# io-board-e-6.net
KiCad netlist of a schematic drawn in EAGLE
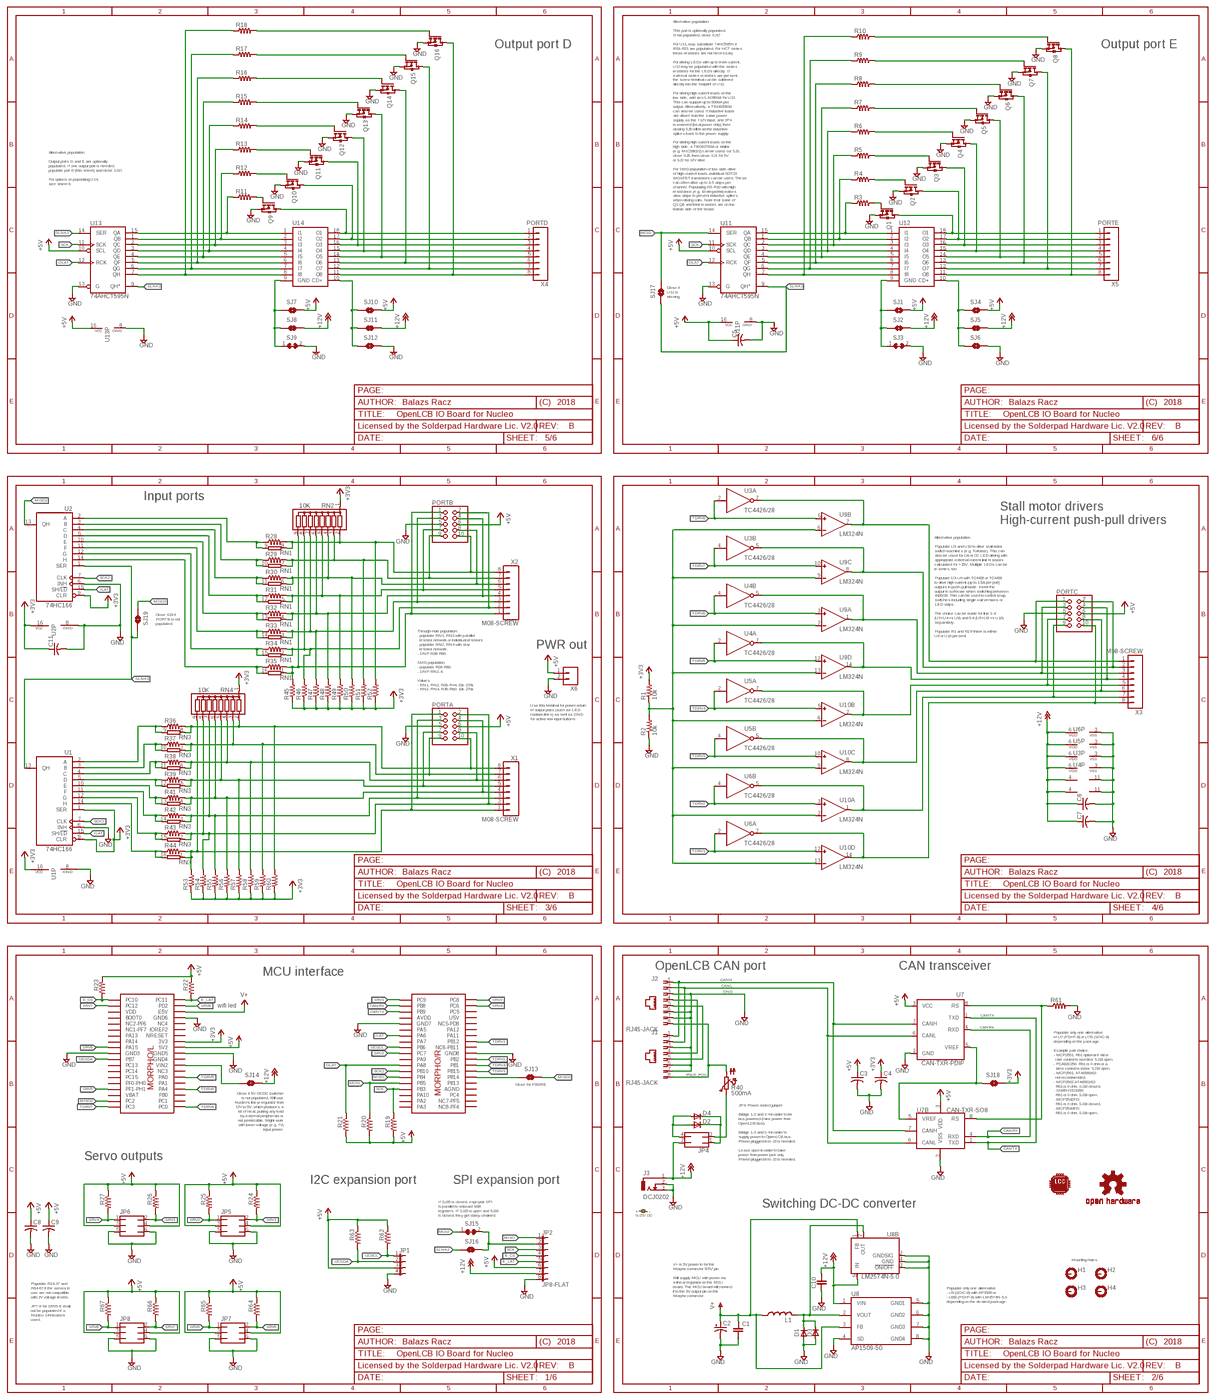
[diagram p0: schematic, sheet 1, overview]
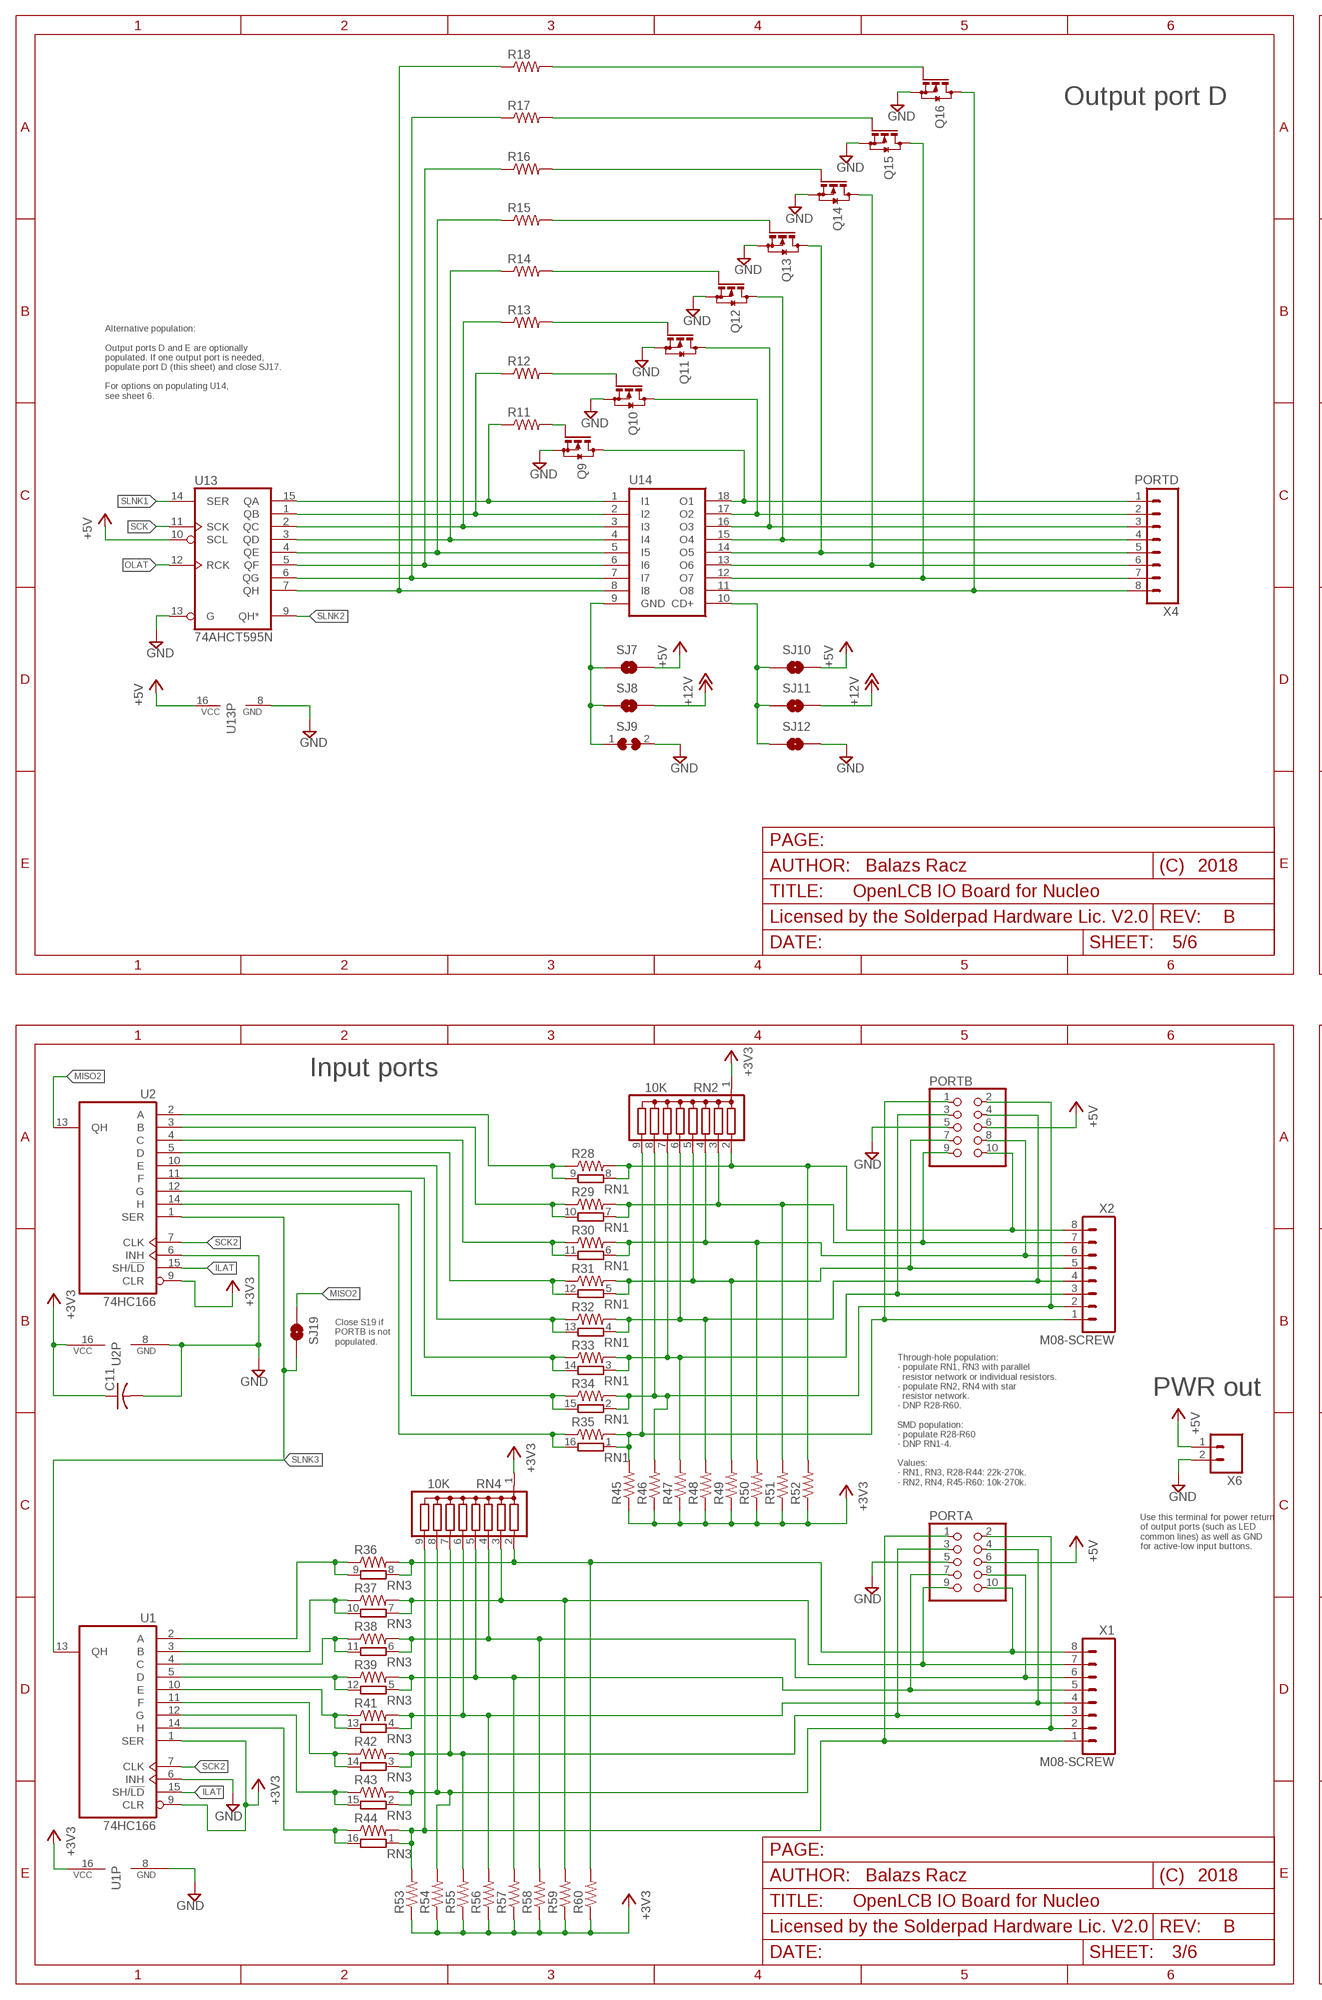
[diagram p1: schematic, sheet 1, part 1 of 4]
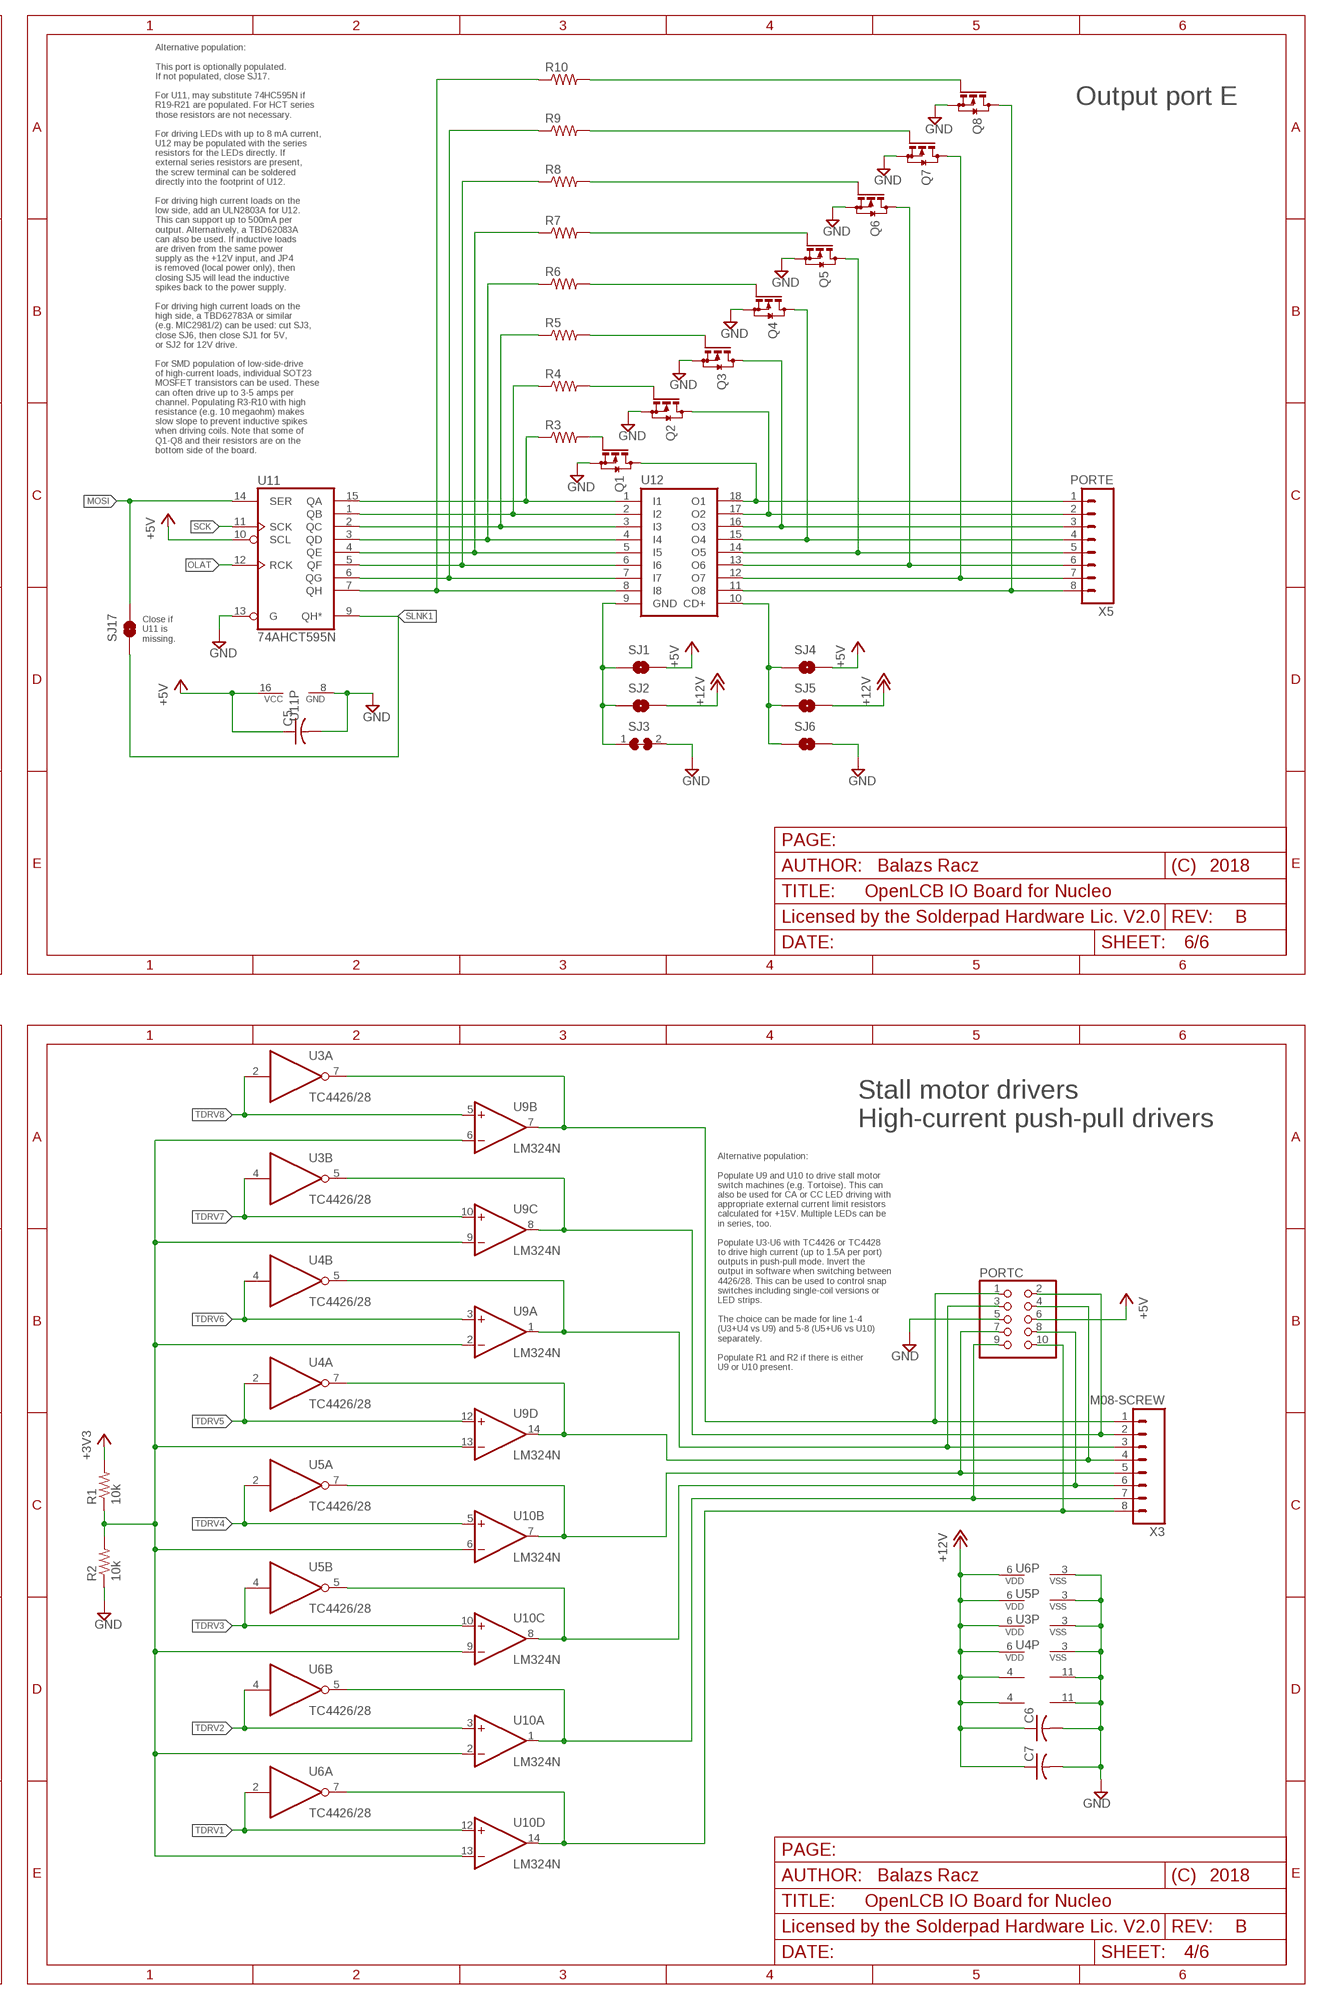
[diagram p2: schematic, sheet 1, part 2 of 4]
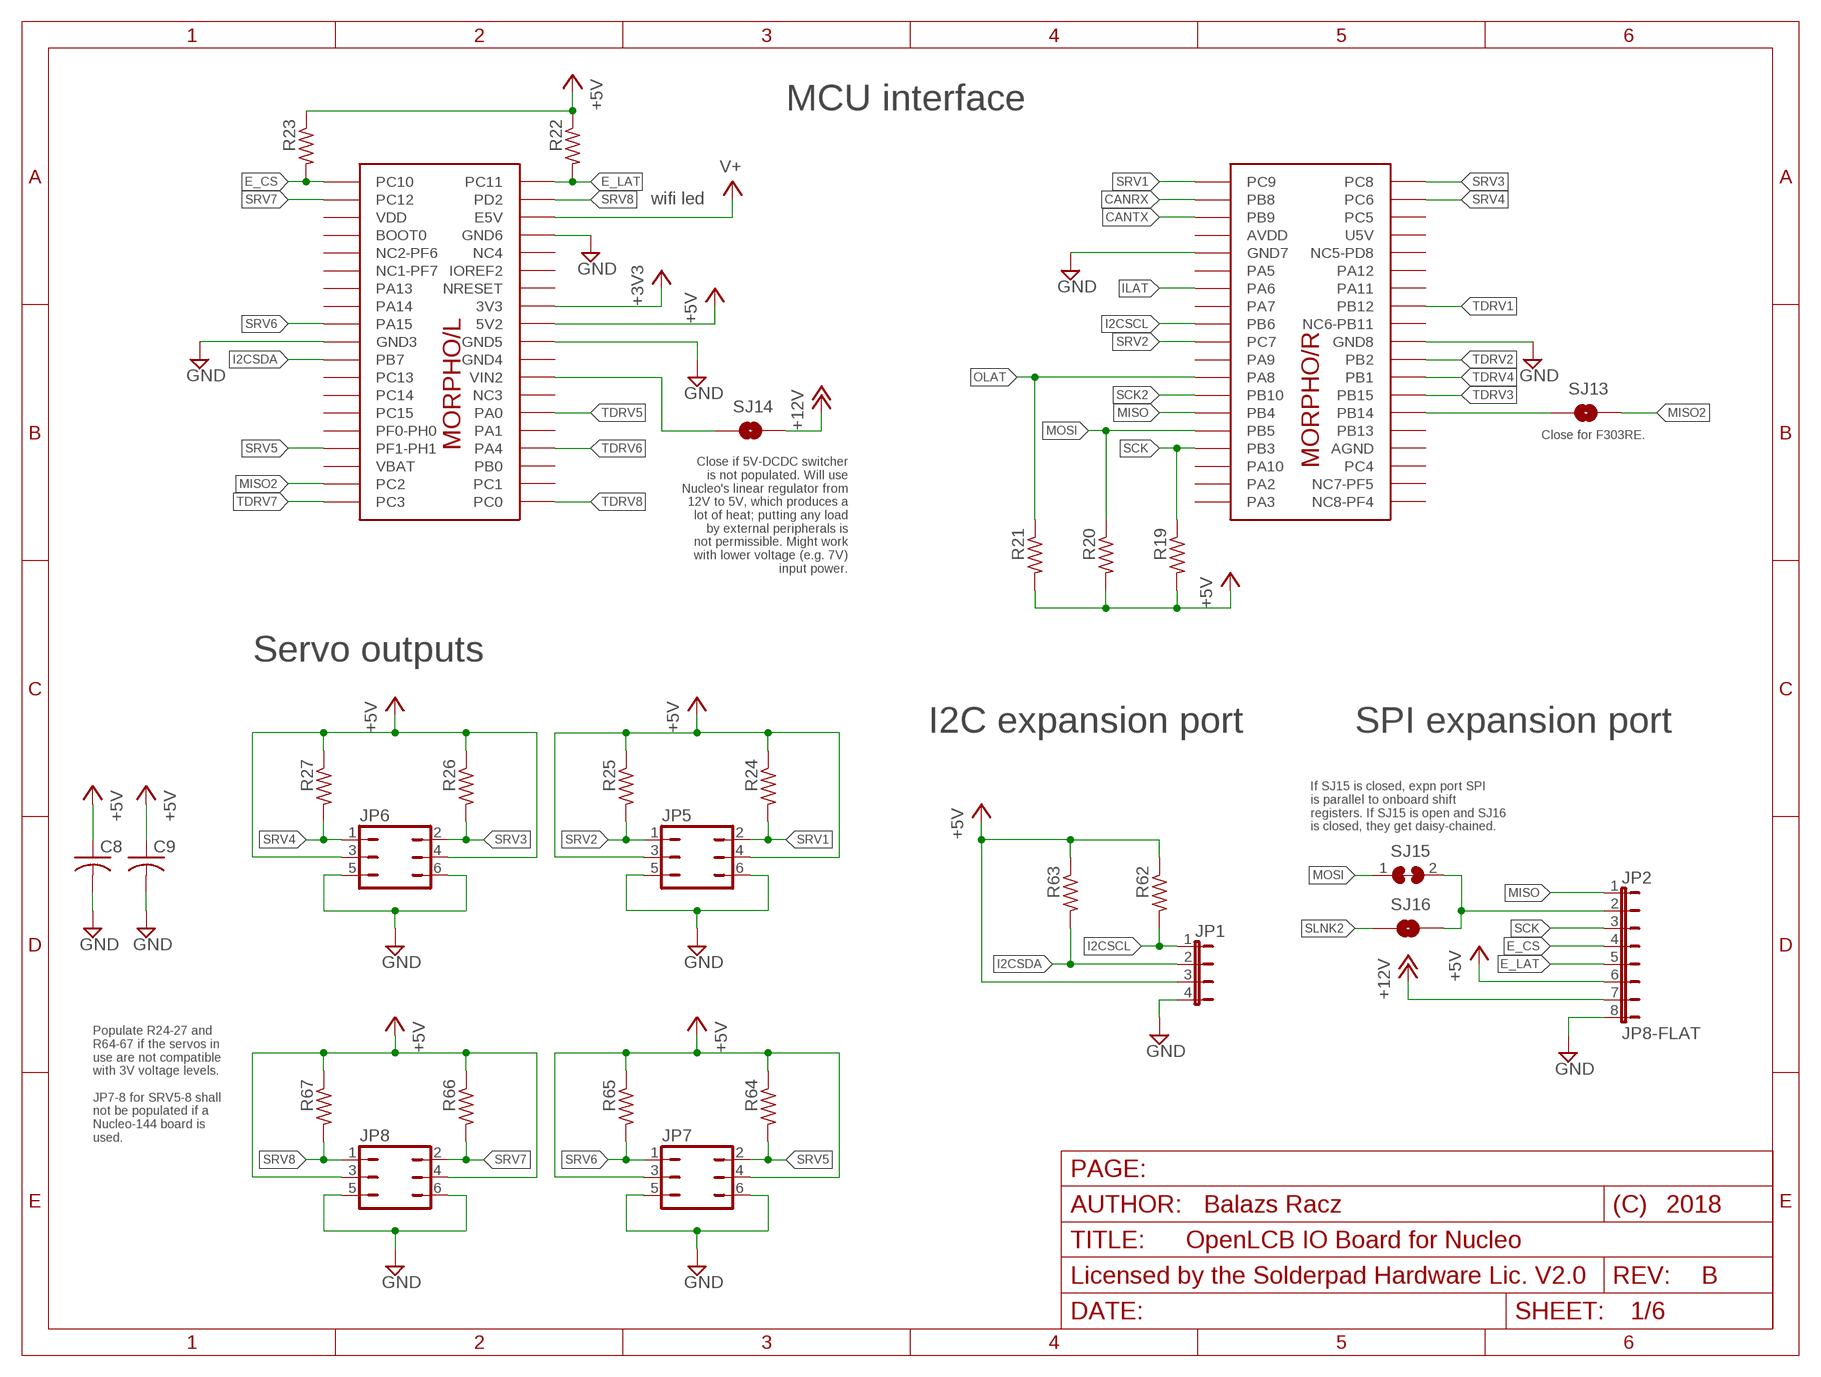
[diagram p3: schematic, sheet 1, part 3 of 4]
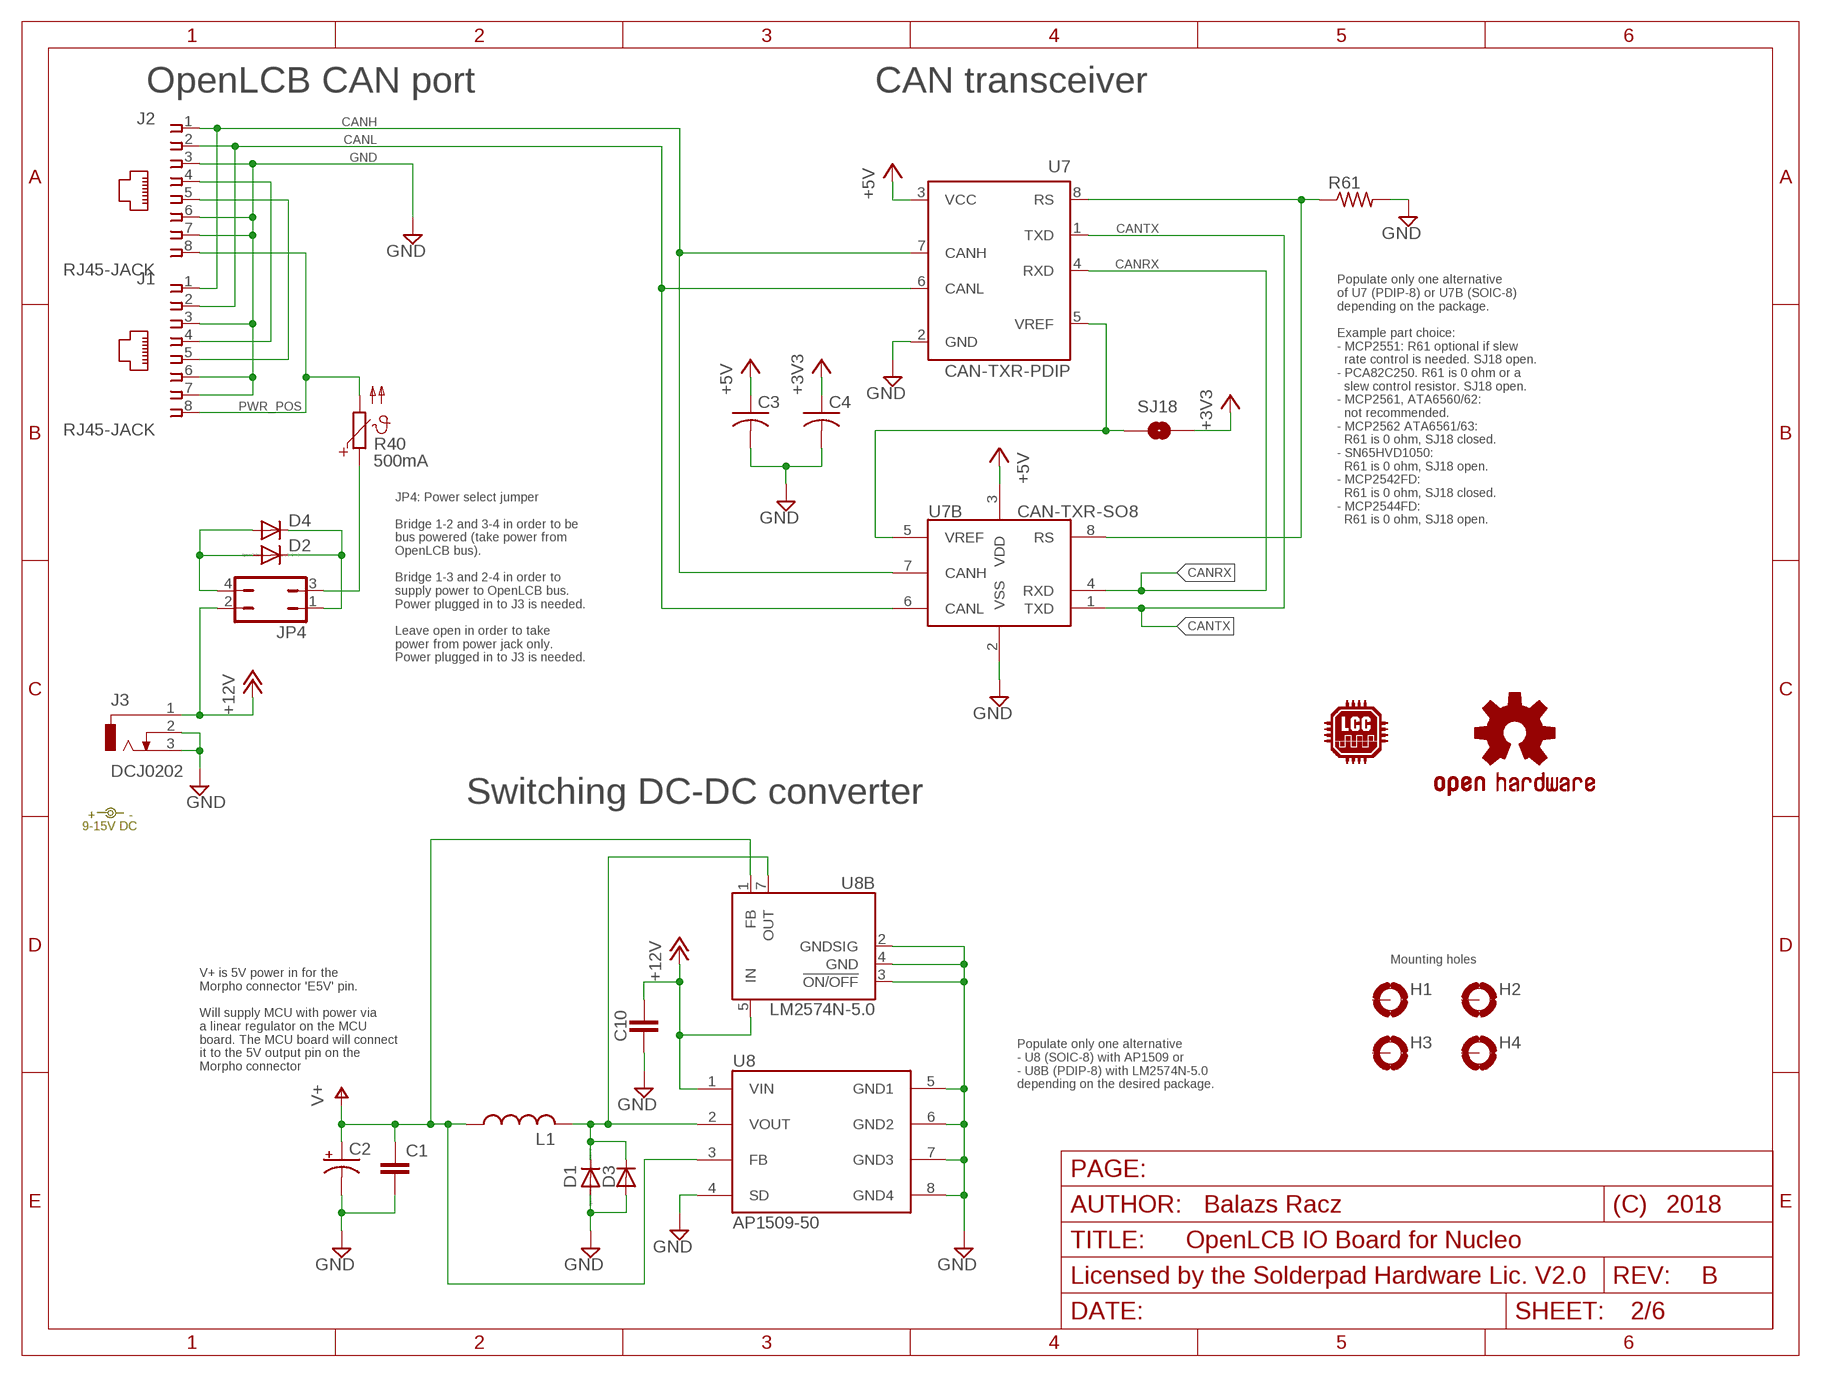
[diagram p4: schematic, sheet 1, part 4 of 4]

(export (version "E")
  (design (tool "Eeschema 10.0.6"))
  (components
    (comp (ref "+12V")
      (value "9-15V DC")
      (footprint "eagle-import:POWER_USAGE")
      (libsource (lib "eagle-import") (part "DOC-POWER_LABEL"))
    )
    (comp (ref "C1")
      (value "C-EUC1206")
      (footprint "eagle-import:C1206")
      (libsource (lib "eagle-import") (part "C-EUC1206"))
    )
    (comp (ref "C2")
      (value "CPOL-USE2.5-5")
      (footprint "eagle-import:E2,5-5")
      (libsource (lib "eagle-import") (part "CPOL-USE2.5-5"))
    )
    (comp (ref "C3")
      (value "C-USC0805")
      (footprint "eagle-import:C0805")
      (libsource (lib "eagle-import") (part "C-USC0805"))
    )
    (comp (ref "C4")
      (value "C-USC0805")
      (footprint "eagle-import:C0805")
      (libsource (lib "eagle-import") (part "C-USC0805"))
    )
    (comp (ref "C5")
      (value "C-USC0805")
      (footprint "eagle-import:C0805")
      (libsource (lib "eagle-import") (part "C-USC0805"))
    )
    (comp (ref "C6")
      (value "C-USC1206")
      (footprint "eagle-import:C1206")
      (libsource (lib "eagle-import") (part "C-USC1206"))
    )
    (comp (ref "C7")
      (value "C-USC1206")
      (footprint "eagle-import:C1206")
      (libsource (lib "eagle-import") (part "C-USC1206"))
    )
    (comp (ref "C8")
      (value "C-USC1206")
      (footprint "eagle-import:C1206")
      (libsource (lib "eagle-import") (part "C-USC1206"))
    )
    (comp (ref "C9")
      (value "C-USC1206")
      (footprint "eagle-import:C1206")
      (libsource (lib "eagle-import") (part "C-USC1206"))
    )
    (comp (ref "C10")
      (value "C-EUC1206")
      (footprint "eagle-import:C1206")
      (libsource (lib "eagle-import") (part "C-EUC1206"))
    )
    (comp (ref "C11")
      (value "C-USC0805")
      (footprint "eagle-import:C0805")
      (libsource (lib "eagle-import") (part "C-USC0805"))
    )
    (comp (ref "D1")
      (value "DIODE-DO41-7.6")
      (footprint "eagle-import:DO41-7.6")
      (libsource (lib "eagle-import") (part "DIODE-DO41-7.6"))
    )
    (comp (ref "D2")
      (value "DIODE-DO41-7.6")
      (footprint "eagle-import:DO41-7.6")
      (libsource (lib "eagle-import") (part "DIODE-DO41-7.6"))
    )
    (comp (ref "D3")
      (value "DIODEDO-214AA-NODOC")
      (footprint "eagle-import:DO214AA-NODOC")
      (libsource (lib "eagle-import") (part "DIODEDO-214AA-NODOC"))
    )
    (comp (ref "D4")
      (value "DIODEDO-214AA-NODOC")
      (footprint "eagle-import:DO214AA-NODOC")
      (libsource (lib "eagle-import") (part "DIODEDO-214AA-NODOC"))
    )
    (comp (ref "H1")
      (value "MOUNT-PAD-ROUND3.3")
      (footprint "eagle-import:3,3-PAD")
      (libsource (lib "eagle-import") (part "MOUNT-PAD-ROUND3.3"))
    )
    (comp (ref "H2")
      (value "MOUNT-PAD-ROUND3.3")
      (footprint "eagle-import:3,3-PAD")
      (libsource (lib "eagle-import") (part "MOUNT-PAD-ROUND3.3"))
    )
    (comp (ref "H3")
      (value "MOUNT-PAD-ROUND3.3")
      (footprint "eagle-import:3,3-PAD")
      (libsource (lib "eagle-import") (part "MOUNT-PAD-ROUND3.3"))
    )
    (comp (ref "H4")
      (value "MOUNT-PAD-ROUND3.3")
      (footprint "eagle-import:3,3-PAD")
      (libsource (lib "eagle-import") (part "MOUNT-PAD-ROUND3.3"))
    )
    (comp (ref "J1")
      (value "RJ45-JACK")
      (footprint "eagle-import:RJ45-PULSE-E5J88")
      (libsource (lib "eagle-import") (part "RJ45-JACKRJ45-PULSE-E5J00"))
    )
    (comp (ref "J2")
      (value "RJ45-JACK")
      (footprint "eagle-import:RJ45-PULSE-E5J88")
      (libsource (lib "eagle-import") (part "RJ45-JACKRJ45-PULSE-E5J00"))
    )
    (comp (ref "J3")
      (value "DCJ0202")
      (footprint "eagle-import:DCJ0202")
      (libsource (lib "eagle-import") (part "DCJ0202"))
    )
    (comp (ref "JP1")
      (value "JP4-FLAT")
      (footprint "eagle-import:JP4F")
      (libsource (lib "eagle-import") (part "JP4-FLAT"))
    )
    (comp (ref "JP2")
      (value "JP8-FLAT")
      (footprint "eagle-import:JP8F")
      (libsource (lib "eagle-import") (part "JP8-FLAT"))
    )
    (comp (ref "JP4")
      (value "JP2Q")
      (footprint "eagle-import:JP2Q")
      (libsource (lib "eagle-import") (part "JP2Q"))
    )
    (comp (ref "JP5")
      (value "JP3Q")
      (footprint "eagle-import:JP3Q")
      (libsource (lib "eagle-import") (part "JP3Q"))
    )
    (comp (ref "JP6")
      (value "JP3Q")
      (footprint "eagle-import:JP3Q")
      (libsource (lib "eagle-import") (part "JP3Q"))
    )
    (comp (ref "JP7")
      (value "JP3Q")
      (footprint "eagle-import:JP3Q")
      (libsource (lib "eagle-import") (part "JP3Q"))
    )
    (comp (ref "JP8")
      (value "JP3Q")
      (footprint "eagle-import:JP3Q")
      (libsource (lib "eagle-import") (part "JP3Q"))
    )
    (comp (ref "L1")
      (value "L-US")
      (footprint "eagle-import:L5-8,5")
      (libsource (lib "eagle-import") (part "L-US"))
    )
    (comp (ref "LG1")
      (value "LCC_LOGO")
      (footprint "eagle-import:LCC_LOGO")
      (libsource (lib "eagle-import") (part "LCC_LOGO"))
    )
    (comp (ref "LOGO1")
      (value "DOC-OSHW-LOGOM")
      (footprint "eagle-import:OSHW-LOGO-M")
      (libsource (lib "eagle-import") (part "DOC-OSHW-LOGOM"))
    )
    (comp (ref "PORTA")
      (value "PINHD-2X5CN")
      (footprint "eagle-import:CON10M")
      (libsource (lib "eagle-import") (part "PINHD-2X5CN"))
    )
    (comp (ref "PORTB")
      (value "PINHD-2X5CN")
      (footprint "eagle-import:CON10M")
      (libsource (lib "eagle-import") (part "PINHD-2X5CN"))
    )
    (comp (ref "PORTC")
      (value "PINHD-2X5CN")
      (footprint "eagle-import:CON10M")
      (libsource (lib "eagle-import") (part "PINHD-2X5CN"))
    )
    (comp (ref "Q1")
      (value "BSS123")
      (footprint "eagle-import:SOT23")
      (libsource (lib "eagle-import") (part "BSS123"))
    )
    (comp (ref "Q2")
      (value "BSS123")
      (footprint "eagle-import:SOT23")
      (libsource (lib "eagle-import") (part "BSS123"))
    )
    (comp (ref "Q3")
      (value "BSS123")
      (footprint "eagle-import:SOT23")
      (libsource (lib "eagle-import") (part "BSS123"))
    )
    (comp (ref "Q4")
      (value "BSS123")
      (footprint "eagle-import:SOT23")
      (libsource (lib "eagle-import") (part "BSS123"))
    )
    (comp (ref "Q5")
      (value "BSS123")
      (footprint "eagle-import:SOT23")
      (libsource (lib "eagle-import") (part "BSS123"))
    )
    (comp (ref "Q6")
      (value "BSS123")
      (footprint "eagle-import:SOT23")
      (libsource (lib "eagle-import") (part "BSS123"))
    )
    (comp (ref "Q7")
      (value "BSS123")
      (footprint "eagle-import:SOT23")
      (libsource (lib "eagle-import") (part "BSS123"))
    )
    (comp (ref "Q8")
      (value "BSS123")
      (footprint "eagle-import:SOT23")
      (libsource (lib "eagle-import") (part "BSS123"))
    )
    (comp (ref "Q9")
      (value "BSS123")
      (footprint "eagle-import:SOT23")
      (libsource (lib "eagle-import") (part "BSS123"))
    )
    (comp (ref "Q10")
      (value "BSS123")
      (footprint "eagle-import:SOT23")
      (libsource (lib "eagle-import") (part "BSS123"))
    )
    (comp (ref "Q11")
      (value "BSS123")
      (footprint "eagle-import:SOT23")
      (libsource (lib "eagle-import") (part "BSS123"))
    )
    (comp (ref "Q12")
      (value "BSS123")
      (footprint "eagle-import:SOT23")
      (libsource (lib "eagle-import") (part "BSS123"))
    )
    (comp (ref "Q13")
      (value "BSS123")
      (footprint "eagle-import:SOT23")
      (libsource (lib "eagle-import") (part "BSS123"))
    )
    (comp (ref "Q14")
      (value "BSS123")
      (footprint "eagle-import:SOT23")
      (libsource (lib "eagle-import") (part "BSS123"))
    )
    (comp (ref "Q15")
      (value "BSS123")
      (footprint "eagle-import:SOT23")
      (libsource (lib "eagle-import") (part "BSS123"))
    )
    (comp (ref "Q16")
      (value "BSS123")
      (footprint "eagle-import:SOT23")
      (libsource (lib "eagle-import") (part "BSS123"))
    )
    (comp (ref "R1")
      (value "10k")
      (footprint "eagle-import:R0805")
      (libsource (lib "eagle-import") (part "R-US_R0805"))
    )
    (comp (ref "R2")
      (value "10k")
      (footprint "eagle-import:R0805")
      (libsource (lib "eagle-import") (part "R-US_R0805"))
    )
    (comp (ref "R3")
      (value "R-US_R0603")
      (footprint "eagle-import:R0603")
      (libsource (lib "eagle-import") (part "R-US_R0603"))
    )
    (comp (ref "R4")
      (value "R-US_R0603")
      (footprint "eagle-import:R0603")
      (libsource (lib "eagle-import") (part "R-US_R0603"))
    )
    (comp (ref "R5")
      (value "R-US_R0603")
      (footprint "eagle-import:R0603")
      (libsource (lib "eagle-import") (part "R-US_R0603"))
    )
    (comp (ref "R6")
      (value "R-US_R0603")
      (footprint "eagle-import:R0603")
      (libsource (lib "eagle-import") (part "R-US_R0603"))
    )
    (comp (ref "R7")
      (value "R-US_R0603")
      (footprint "eagle-import:R0603")
      (libsource (lib "eagle-import") (part "R-US_R0603"))
    )
    (comp (ref "R8")
      (value "R-US_R0603")
      (footprint "eagle-import:R0603")
      (libsource (lib "eagle-import") (part "R-US_R0603"))
    )
    (comp (ref "R9")
      (value "R-US_R0603")
      (footprint "eagle-import:R0603")
      (libsource (lib "eagle-import") (part "R-US_R0603"))
    )
    (comp (ref "R10")
      (value "R-US_R0603")
      (footprint "eagle-import:R0603")
      (libsource (lib "eagle-import") (part "R-US_R0603"))
    )
    (comp (ref "R11")
      (value "R-US_R0603")
      (footprint "eagle-import:R0603")
      (libsource (lib "eagle-import") (part "R-US_R0603"))
    )
    (comp (ref "R12")
      (value "R-US_R0603")
      (footprint "eagle-import:R0603")
      (libsource (lib "eagle-import") (part "R-US_R0603"))
    )
    (comp (ref "R13")
      (value "R-US_R0603")
      (footprint "eagle-import:R0603")
      (libsource (lib "eagle-import") (part "R-US_R0603"))
    )
    (comp (ref "R14")
      (value "R-US_R0603")
      (footprint "eagle-import:R0603")
      (libsource (lib "eagle-import") (part "R-US_R0603"))
    )
    (comp (ref "R15")
      (value "R-US_R0603")
      (footprint "eagle-import:R0603")
      (libsource (lib "eagle-import") (part "R-US_R0603"))
    )
    (comp (ref "R16")
      (value "R-US_R0603")
      (footprint "eagle-import:R0603")
      (libsource (lib "eagle-import") (part "R-US_R0603"))
    )
    (comp (ref "R17")
      (value "R-US_R0603")
      (footprint "eagle-import:R0603")
      (libsource (lib "eagle-import") (part "R-US_R0603"))
    )
    (comp (ref "R18")
      (value "R-US_R0603")
      (footprint "eagle-import:R0603")
      (libsource (lib "eagle-import") (part "R-US_R0603"))
    )
    (comp (ref "R19")
      (value "R-US_R0805")
      (footprint "eagle-import:R0805")
      (libsource (lib "eagle-import") (part "rcl_334_R-US_R0805"))
    )
    (comp (ref "R20")
      (value "R-US_R0805")
      (footprint "eagle-import:R0805")
      (libsource (lib "eagle-import") (part "rcl_334_R-US_R0805"))
    )
    (comp (ref "R21")
      (value "R-US_R0805")
      (footprint "eagle-import:R0805")
      (libsource (lib "eagle-import") (part "rcl_334_R-US_R0805"))
    )
    (comp (ref "R22")
      (value "R-US_R0805")
      (footprint "eagle-import:R0805")
      (libsource (lib "eagle-import") (part "rcl_334_R-US_R0805"))
    )
    (comp (ref "R23")
      (value "R-US_R0805")
      (footprint "eagle-import:R0805")
      (libsource (lib "eagle-import") (part "rcl_334_R-US_R0805"))
    )
    (comp (ref "R24")
      (value "R-US_R0805")
      (footprint "eagle-import:R0805")
      (libsource (lib "eagle-import") (part "rcl_334_R-US_R0805"))
    )
    (comp (ref "R25")
      (value "R-US_R0805")
      (footprint "eagle-import:R0805")
      (libsource (lib "eagle-import") (part "rcl_334_R-US_R0805"))
    )
    (comp (ref "R26")
      (value "R-US_R0805")
      (footprint "eagle-import:R0805")
      (libsource (lib "eagle-import") (part "rcl_334_R-US_R0805"))
    )
    (comp (ref "R27")
      (value "R-US_R0805")
      (footprint "eagle-import:R0805")
      (libsource (lib "eagle-import") (part "rcl_334_R-US_R0805"))
    )
    (comp (ref "R28")
      (value "R-US_R0603")
      (footprint "eagle-import:R0603")
      (libsource (lib "eagle-import") (part "rcl_334_R-US_R0603"))
    )
    (comp (ref "R29")
      (value "R-US_R0603")
      (footprint "eagle-import:R0603")
      (libsource (lib "eagle-import") (part "rcl_334_R-US_R0603"))
    )
    (comp (ref "R30")
      (value "R-US_R0603")
      (footprint "eagle-import:R0603")
      (libsource (lib "eagle-import") (part "rcl_334_R-US_R0603"))
    )
    (comp (ref "R31")
      (value "R-US_R0603")
      (footprint "eagle-import:R0603")
      (libsource (lib "eagle-import") (part "rcl_334_R-US_R0603"))
    )
    (comp (ref "R32")
      (value "R-US_R0603")
      (footprint "eagle-import:R0603")
      (libsource (lib "eagle-import") (part "rcl_334_R-US_R0603"))
    )
    (comp (ref "R33")
      (value "R-US_R0603")
      (footprint "eagle-import:R0603")
      (libsource (lib "eagle-import") (part "rcl_334_R-US_R0603"))
    )
    (comp (ref "R34")
      (value "R-US_R0603")
      (footprint "eagle-import:R0603")
      (libsource (lib "eagle-import") (part "rcl_334_R-US_R0603"))
    )
    (comp (ref "R35")
      (value "R-US_R0603")
      (footprint "eagle-import:R0603")
      (libsource (lib "eagle-import") (part "rcl_334_R-US_R0603"))
    )
    (comp (ref "R36")
      (value "R-US_R0603")
      (footprint "eagle-import:R0603")
      (libsource (lib "eagle-import") (part "rcl_334_R-US_R0603"))
    )
    (comp (ref "R37")
      (value "R-US_R0603")
      (footprint "eagle-import:R0603")
      (libsource (lib "eagle-import") (part "rcl_334_R-US_R0603"))
    )
    (comp (ref "R38")
      (value "R-US_R0603")
      (footprint "eagle-import:R0603")
      (libsource (lib "eagle-import") (part "rcl_334_R-US_R0603"))
    )
    (comp (ref "R39")
      (value "R-US_R0603")
      (footprint "eagle-import:R0603")
      (libsource (lib "eagle-import") (part "rcl_334_R-US_R0603"))
    )
    (comp (ref "R40")
      (value "500mA")
      (footprint "eagle-import:PTC1812")
      (libsource (lib "eagle-import") (part "PTC_1812"))
    )
    (comp (ref "R41")
      (value "R-US_R0603")
      (footprint "eagle-import:R0603")
      (libsource (lib "eagle-import") (part "rcl_334_R-US_R0603"))
    )
    (comp (ref "R42")
      (value "R-US_R0603")
      (footprint "eagle-import:R0603")
      (libsource (lib "eagle-import") (part "rcl_334_R-US_R0603"))
    )
    (comp (ref "R43")
      (value "R-US_R0603")
      (footprint "eagle-import:R0603")
      (libsource (lib "eagle-import") (part "rcl_334_R-US_R0603"))
    )
    (comp (ref "R44")
      (value "R-US_R0603")
      (footprint "eagle-import:R0603")
      (libsource (lib "eagle-import") (part "rcl_334_R-US_R0603"))
    )
    (comp (ref "R45")
      (value "R-US")
      (footprint "eagle-import:R0603")
      (libsource (lib "eagle-import") (part "R-US"))
    )
    (comp (ref "R46")
      (value "R-US")
      (footprint "eagle-import:R0603")
      (libsource (lib "eagle-import") (part "R-US"))
    )
    (comp (ref "R47")
      (value "R-US")
      (footprint "eagle-import:R0603")
      (libsource (lib "eagle-import") (part "R-US"))
    )
    (comp (ref "R48")
      (value "R-US")
      (footprint "eagle-import:R0603")
      (libsource (lib "eagle-import") (part "R-US"))
    )
    (comp (ref "R49")
      (value "R-US")
      (footprint "eagle-import:R0603")
      (libsource (lib "eagle-import") (part "R-US"))
    )
    (comp (ref "R50")
      (value "R-US")
      (footprint "eagle-import:R0603")
      (libsource (lib "eagle-import") (part "R-US"))
    )
    (comp (ref "R51")
      (value "R-US")
      (footprint "eagle-import:R0603")
      (libsource (lib "eagle-import") (part "R-US"))
    )
    (comp (ref "R52")
      (value "R-US")
      (footprint "eagle-import:R0603")
      (libsource (lib "eagle-import") (part "R-US"))
    )
    (comp (ref "R53")
      (value "R-US")
      (footprint "eagle-import:R0603")
      (libsource (lib "eagle-import") (part "R-US"))
    )
    (comp (ref "R54")
      (value "R-US")
      (footprint "eagle-import:R0603")
      (libsource (lib "eagle-import") (part "R-US"))
    )
    (comp (ref "R55")
      (value "R-US")
      (footprint "eagle-import:R0603")
      (libsource (lib "eagle-import") (part "R-US"))
    )
    (comp (ref "R56")
      (value "R-US")
      (footprint "eagle-import:R0603")
      (libsource (lib "eagle-import") (part "R-US"))
    )
    (comp (ref "R57")
      (value "R-US")
      (footprint "eagle-import:R0603")
      (libsource (lib "eagle-import") (part "R-US"))
    )
    (comp (ref "R58")
      (value "R-US")
      (footprint "eagle-import:R0603")
      (libsource (lib "eagle-import") (part "R-US"))
    )
    (comp (ref "R59")
      (value "R-US")
      (footprint "eagle-import:R0603")
      (libsource (lib "eagle-import") (part "R-US"))
    )
    (comp (ref "R60")
      (value "R-US")
      (footprint "eagle-import:R0603")
      (libsource (lib "eagle-import") (part "R-US"))
    )
    (comp (ref "R61")
      (value "R-US_R0805")
      (footprint "eagle-import:R0805")
      (libsource (lib "eagle-import") (part "rcl_334_R-US_R0805"))
    )
    (comp (ref "R62")
      (value "R-US_R0805")
      (footprint "eagle-import:R0805")
      (libsource (lib "eagle-import") (part "rcl_334_R-US_R0805"))
    )
    (comp (ref "R63")
      (value "R-US_R0805")
      (footprint "eagle-import:R0805")
      (libsource (lib "eagle-import") (part "rcl_334_R-US_R0805"))
    )
    (comp (ref "R64")
      (value "R-US_R0805")
      (footprint "eagle-import:R0805")
      (libsource (lib "eagle-import") (part "rcl_334_R-US_R0805"))
    )
    (comp (ref "R65")
      (value "R-US_R0805")
      (footprint "eagle-import:R0805")
      (libsource (lib "eagle-import") (part "rcl_334_R-US_R0805"))
    )
    (comp (ref "R66")
      (value "R-US_R0805")
      (footprint "eagle-import:R0805")
      (libsource (lib "eagle-import") (part "rcl_334_R-US_R0805"))
    )
    (comp (ref "R67")
      (value "R-US_R0805")
      (footprint "eagle-import:R0805")
      (libsource (lib "eagle-import") (part "rcl_334_R-US_R0805"))
    )
    (comp (ref "RN1")
      (value "8R-P")
      (footprint "eagle-import:DIL16")
      (libsource (lib "eagle-import") (part "8R-P"))
    )
    (comp (ref "RN2")
      (value "10K")
      (footprint "eagle-import:SIL9")
      (libsource (lib "eagle-import") (part "G08R"))
    )
    (comp (ref "RN3")
      (value "8R-P")
      (footprint "eagle-import:DIL16")
      (libsource (lib "eagle-import") (part "8R-P"))
    )
    (comp (ref "RN4")
      (value "10K")
      (footprint "eagle-import:SIL9")
      (libsource (lib "eagle-import") (part "G08R"))
    )
    (comp (ref "SJ1")
      (value "SJRND2")
      (footprint "eagle-import:SJ_RND2")
      (libsource (lib "eagle-import") (part "SJRND2"))
    )
    (comp (ref "SJ2")
      (value "SJRND2")
      (footprint "eagle-import:SJ_RND2")
      (libsource (lib "eagle-import") (part "SJRND2"))
    )
    (comp (ref "SJ3")
      (value "SJ-C")
      (footprint "eagle-import:SJW-C")
      (libsource (lib "eagle-import") (part "SJ-C"))
    )
    (comp (ref "SJ4")
      (value "SJRND2")
      (footprint "eagle-import:SJ_RND2")
      (libsource (lib "eagle-import") (part "SJRND2"))
    )
    (comp (ref "SJ5")
      (value "SJRND2")
      (footprint "eagle-import:SJ_RND2")
      (libsource (lib "eagle-import") (part "SJRND2"))
    )
    (comp (ref "SJ6")
      (value "SJRND2")
      (footprint "eagle-import:SJ_RND2")
      (libsource (lib "eagle-import") (part "SJRND2"))
    )
    (comp (ref "SJ7")
      (value "SJRND2")
      (footprint "eagle-import:SJ_RND2")
      (libsource (lib "eagle-import") (part "SJRND2"))
    )
    (comp (ref "SJ8")
      (value "SJRND2")
      (footprint "eagle-import:SJ_RND2")
      (libsource (lib "eagle-import") (part "SJRND2"))
    )
    (comp (ref "SJ9")
      (value "SJ-C")
      (footprint "eagle-import:SJW-C")
      (libsource (lib "eagle-import") (part "SJ-C"))
    )
    (comp (ref "SJ10")
      (value "SJRND2")
      (footprint "eagle-import:SJ_RND2")
      (libsource (lib "eagle-import") (part "SJRND2"))
    )
    (comp (ref "SJ11")
      (value "SJRND2")
      (footprint "eagle-import:SJ_RND2")
      (libsource (lib "eagle-import") (part "SJRND2"))
    )
    (comp (ref "SJ12")
      (value "SJRND2")
      (footprint "eagle-import:SJ_RND2")
      (libsource (lib "eagle-import") (part "SJRND2"))
    )
    (comp (ref "SJ13")
      (value "SJRND2")
      (footprint "eagle-import:SJ_RND2")
      (libsource (lib "eagle-import") (part "SJRND2"))
    )
    (comp (ref "SJ14")
      (value "SJRND2")
      (footprint "eagle-import:SJ_RND2")
      (libsource (lib "eagle-import") (part "SJRND2"))
    )
    (comp (ref "SJ15")
      (value "SJ-C")
      (footprint "eagle-import:SJW-C")
      (libsource (lib "eagle-import") (part "SJ-C"))
    )
    (comp (ref "SJ16")
      (value "SJRND2")
      (footprint "eagle-import:SJ_RND2")
      (libsource (lib "eagle-import") (part "SJRND2"))
    )
    (comp (ref "SJ17")
      (value "SJRND2")
      (footprint "eagle-import:SJ_RND2")
      (libsource (lib "eagle-import") (part "SJRND2"))
    )
    (comp (ref "SJ18")
      (value "SJRND2")
      (footprint "eagle-import:SJ_RND2")
      (libsource (lib "eagle-import") (part "SJRND2"))
    )
    (comp (ref "SJ19")
      (value "SJRND2")
      (footprint "eagle-import:SJ_RND2")
      (libsource (lib "eagle-import") (part "SJRND2"))
    )
    (comp (ref "U$1")
      (value "NUCLEO_64_GENERIC")
      (footprint "eagle-import:NUCLEO_BRD_BASE64")
      (libsource (lib "eagle-import") (part "NUCLEO_64_GENERIC"))
    )
    (comp (ref "U1")
      (value "74HC166")
      (footprint "eagle-import:DIL16")
      (libsource (lib "eagle-import") (part "74166N"))
    )
    (comp (ref "U2")
      (value "74HC166")
      (footprint "eagle-import:DIL16")
      (libsource (lib "eagle-import") (part "74166N"))
    )
    (comp (ref "U3")
      (value "TC4426/28")
      (footprint "eagle-import:DIL08-LONG")
      (libsource (lib "eagle-import") (part "TC4426APDIP"))
    )
    (comp (ref "U4")
      (value "TC4426/28")
      (footprint "eagle-import:DIL08-LONG")
      (libsource (lib "eagle-import") (part "TC4426APDIP"))
    )
    (comp (ref "U5")
      (value "TC4426/28")
      (footprint "eagle-import:DIL08-LONG")
      (libsource (lib "eagle-import") (part "TC4426APDIP"))
    )
    (comp (ref "U6")
      (value "TC4426/28")
      (footprint "eagle-import:DIL08-LONG")
      (libsource (lib "eagle-import") (part "TC4426APDIP"))
    )
    (comp (ref "U7")
      (value "CAN-TXR-PDIP")
      (footprint "eagle-import:DIL08")
      (libsource (lib "eagle-import") (part "PCA82C250"))
    )
    (comp (ref "U7B")
      (value "CAN-TXR-SO8")
      (footprint "eagle-import:SO-08")
      (libsource (lib "eagle-import") (part "MCP2551-SN"))
    )
    (comp (ref "U8")
      (value "AP1509-50")
      (footprint "eagle-import:SO-08")
      (libsource (lib "eagle-import") (part "AP1509"))
    )
    (comp (ref "U8B")
      (value "LM2574N-5.0")
      (footprint "eagle-import:DIL08")
      (libsource (lib "eagle-import") (part "LM2574?-N5.0"))
    )
    (comp (ref "U9")
      (value "LM324N")
      (footprint "eagle-import:DIL14")
      (libsource (lib "eagle-import") (part "LM324N"))
    )
    (comp (ref "U10")
      (value "LM324N")
      (footprint "eagle-import:DIL14")
      (libsource (lib "eagle-import") (part "LM324N"))
    )
    (comp (ref "U11")
      (value "74AHCT595N")
      (footprint "eagle-import:DIL16")
      (libsource (lib "eagle-import") (part "74595NHCT"))
    )
    (comp (ref "U12")
      (value "ULN2803A")
      (footprint "eagle-import:DIL18-THIN")
      (libsource (lib "eagle-import") (part "ULN2803A"))
    )
    (comp (ref "U13")
      (value "74AHCT595N")
      (footprint "eagle-import:DIL16")
      (libsource (lib "eagle-import") (part "74595NHCT"))
    )
    (comp (ref "U14")
      (value "ULN2803A")
      (footprint "eagle-import:DIL18-THIN")
      (libsource (lib "eagle-import") (part "ULN2803A"))
    )
    (comp (ref "X1")
      (value "M08-SCREW")
      (footprint "eagle-import:1X08_TERMINAL")
      (libsource (lib "eagle-import") (part "M08-SCREW"))
    )
    (comp (ref "X2")
      (value "M08-SCREW")
      (footprint "eagle-import:1X08_TERMINAL")
      (libsource (lib "eagle-import") (part "M08-SCREW"))
    )
    (comp (ref "X3")
      (value "M08-SCREW")
      (footprint "eagle-import:1X08_TERMINAL")
      (libsource (lib "eagle-import") (part "M08-SCREW"))
    )
    (comp (ref "X4")
      (value "PORTD")
      (footprint "eagle-import:1X08_TERMINAL")
      (libsource (lib "eagle-import") (part "M08-SCREW"))
    )
    (comp (ref "X5")
      (value "PORTE")
      (footprint "eagle-import:1X08_TERMINAL")
      (libsource (lib "eagle-import") (part "M08-SCREW"))
    )
    (comp (ref "X6")
      (value "CONNECTOR-M023.5MM-LOCK")
      (footprint "eagle-import:SCREWTERMINAL-3.5MM-2_LOCK")
      (libsource (lib "eagle-import") (part "CONNECTOR-M023.5MM-LOCK"))
    )
  )
  (nets
    (net (code "1") (name "+3V3") (class "Default")
      (node (ref "C11") (pin "1") (pinfunction "1_1") (pintype "passive"))
      (node (ref "C4") (pin "1") (pinfunction "1_1") (pintype "passive"))
      (node (ref "R1") (pin "2") (pinfunction "2_2") (pintype "passive"))
      (node (ref "R45") (pin "1") (pinfunction "1_1") (pintype "passive"))
      (node (ref "R46") (pin "1") (pinfunction "1_1") (pintype "passive"))
      (node (ref "R47") (pin "1") (pinfunction "1_1") (pintype "passive"))
      (node (ref "R48") (pin "1") (pinfunction "1_1") (pintype "passive"))
      (node (ref "R49") (pin "1") (pinfunction "1_1") (pintype "passive"))
      (node (ref "R50") (pin "1") (pinfunction "1_1") (pintype "passive"))
      (node (ref "R51") (pin "1") (pinfunction "1_1") (pintype "passive"))
      (node (ref "R52") (pin "1") (pinfunction "1_1") (pintype "passive"))
      (node (ref "R53") (pin "1") (pinfunction "1_1") (pintype "passive"))
      (node (ref "R54") (pin "1") (pinfunction "1_1") (pintype "passive"))
      (node (ref "R55") (pin "1") (pinfunction "1_1") (pintype "passive"))
      (node (ref "R56") (pin "1") (pinfunction "1_1") (pintype "passive"))
      (node (ref "R57") (pin "1") (pinfunction "1_1") (pintype "passive"))
      (node (ref "R58") (pin "1") (pinfunction "1_1") (pintype "passive"))
      (node (ref "R59") (pin "1") (pinfunction "1_1") (pintype "passive"))
      (node (ref "R60") (pin "1") (pinfunction "1_1") (pintype "passive"))
      (node (ref "RN2") (pin "1") (pinfunction "1_1") (pintype "passive"))
      (node (ref "RN4") (pin "1") (pinfunction "1_1") (pintype "passive"))
      (node (ref "SJ18") (pin "P$1") (pinfunction "1_P$1") (pintype "passive"))
      (node (ref "U$1") (pin "3V3") (pinfunction "3V3_3V3") (pintype "power_in"))
      (node (ref "U1") (pin "1") (pinfunction "SER_1") (pintype "input"))
      (node (ref "U1") (pin "16") (pinfunction "VCC_16") (pintype "power_in"))
      (node (ref "U1") (pin "9") (pinfunction "CLR_9") (pintype "input"))
      (node (ref "U2") (pin "16") (pinfunction "VCC_16") (pintype "power_in"))
      (node (ref "U2") (pin "9") (pinfunction "CLR_9") (pintype "input"))
    )
    (net (code "2") (name "+5V") (class "Default")
      (node (ref "C3") (pin "1") (pinfunction "1_1") (pintype "passive"))
      (node (ref "C5") (pin "1") (pinfunction "1_1") (pintype "passive"))
      (node (ref "C8") (pin "1") (pinfunction "1_1") (pintype "passive"))
      (node (ref "C9") (pin "1") (pinfunction "1_1") (pintype "passive"))
      (node (ref "JP1") (pin "3") (pinfunction "3_3") (pintype "passive"))
      (node (ref "JP2") (pin "6") (pinfunction "6_6") (pintype "passive"))
      (node (ref "JP5") (pin "3") (pinfunction "3_3") (pintype "passive"))
      (node (ref "JP5") (pin "4") (pinfunction "4_4") (pintype "passive"))
      (node (ref "JP6") (pin "3") (pinfunction "3_3") (pintype "passive"))
      (node (ref "JP6") (pin "4") (pinfunction "4_4") (pintype "passive"))
      (node (ref "JP7") (pin "3") (pinfunction "3_3") (pintype "passive"))
      (node (ref "JP7") (pin "4") (pinfunction "4_4") (pintype "passive"))
      (node (ref "JP8") (pin "3") (pinfunction "3_3") (pintype "passive"))
      (node (ref "JP8") (pin "4") (pinfunction "4_4") (pintype "passive"))
      (node (ref "PORTA") (pin "6") (pinfunction "6_6") (pintype "passive"))
      (node (ref "PORTB") (pin "6") (pinfunction "6_6") (pintype "passive"))
      (node (ref "PORTC") (pin "6") (pinfunction "6_6") (pintype "passive"))
      (node (ref "R19") (pin "2") (pinfunction "2_2") (pintype "passive"))
      (node (ref "R20") (pin "2") (pinfunction "2_2") (pintype "passive"))
      (node (ref "R21") (pin "2") (pinfunction "2_2") (pintype "passive"))
      (node (ref "R22") (pin "1") (pinfunction "1_1") (pintype "passive"))
      (node (ref "R23") (pin "1") (pinfunction "1_1") (pintype "passive"))
      (node (ref "R24") (pin "1") (pinfunction "1_1") (pintype "passive"))
      (node (ref "R25") (pin "1") (pinfunction "1_1") (pintype "passive"))
      (node (ref "R26") (pin "1") (pinfunction "1_1") (pintype "passive"))
      (node (ref "R27") (pin "1") (pinfunction "1_1") (pintype "passive"))
      (node (ref "R62") (pin "1") (pinfunction "1_1") (pintype "passive"))
      (node (ref "R63") (pin "1") (pinfunction "1_1") (pintype "passive"))
      (node (ref "R64") (pin "1") (pinfunction "1_1") (pintype "passive"))
      (node (ref "R65") (pin "1") (pinfunction "1_1") (pintype "passive"))
      (node (ref "R66") (pin "1") (pinfunction "1_1") (pintype "passive"))
      (node (ref "R67") (pin "1") (pinfunction "1_1") (pintype "passive"))
      (node (ref "SJ1") (pin "P$2") (pinfunction "2_P$2") (pintype "passive"))
      (node (ref "SJ10") (pin "P$2") (pinfunction "2_P$2") (pintype "passive"))
      (node (ref "SJ4") (pin "P$2") (pinfunction "2_P$2") (pintype "passive"))
      (node (ref "SJ7") (pin "P$2") (pinfunction "2_P$2") (pintype "passive"))
      (node (ref "U$1") (pin "5V2") (pinfunction "5V2_5V2") (pintype "power_in"))
      (node (ref "U11") (pin "10") (pinfunction "SCL_10") (pintype "input"))
      (node (ref "U11") (pin "16") (pinfunction "VCC_16") (pintype "power_in"))
      (node (ref "U13") (pin "10") (pinfunction "SCL_10") (pintype "input"))
      (node (ref "U13") (pin "16") (pinfunction "VCC_16") (pintype "power_in"))
      (node (ref "U7") (pin "3") (pinfunction "VCC_3") (pintype "power_in"))
      (node (ref "U7B") (pin "3") (pinfunction "VDD_3") (pintype "power_in"))
      (node (ref "X6") (pin "1") (pinfunction "1_1") (pintype "passive"))
    )
    (net (code "3") (name "+12V") (class "Default")
      (node (ref "C10") (pin "1") (pinfunction "1_1") (pintype "passive"))
      (node (ref "C6") (pin "1") (pinfunction "1_1") (pintype "passive"))
      (node (ref "C7") (pin "1") (pinfunction "1_1") (pintype "passive"))
      (node (ref "J3") (pin "1") (pinfunction "1_1") (pintype "passive"))
      (node (ref "JP2") (pin "7") (pinfunction "7_7") (pintype "passive"))
      (node (ref "JP4") (pin "2") (pinfunction "2_2") (pintype "passive"))
      (node (ref "SJ11") (pin "P$2") (pinfunction "2_P$2") (pintype "passive"))
      (node (ref "SJ14") (pin "P$2") (pinfunction "2_P$2") (pintype "passive"))
      (node (ref "SJ2") (pin "P$2") (pinfunction "2_P$2") (pintype "passive"))
      (node (ref "SJ5") (pin "P$2") (pinfunction "2_P$2") (pintype "passive"))
      (node (ref "SJ8") (pin "P$2") (pinfunction "2_P$2") (pintype "passive"))
      (node (ref "U10") (pin "4") (pinfunction "V+_4") (pintype "power_in"))
      (node (ref "U3") (pin "6") (pinfunction "VDD_6") (pintype "power_in"))
      (node (ref "U4") (pin "6") (pinfunction "VDD_6") (pintype "power_in"))
      (node (ref "U5") (pin "6") (pinfunction "VDD_6") (pintype "power_in"))
      (node (ref "U6") (pin "6") (pinfunction "VDD_6") (pintype "power_in"))
      (node (ref "U8") (pin "1") (pinfunction "VIN_1") (pintype "bidirectional"))
      (node (ref "U8B") (pin "5") (pinfunction "IN_5") (pintype "input"))
      (node (ref "U9") (pin "4") (pinfunction "V+_4") (pintype "power_in"))
    )
    (net (code "4") (name "/AGND") (class "Default")
      (node (ref "U$1") (pin "AGND") (pinfunction "AGND_AGND") (pintype "power_in"))
    )
    (net (code "5") (name "/AVDD") (class "Default")
      (node (ref "U$1") (pin "AVDD") (pinfunction "AVDD_AVDD") (pintype "power_in"))
    )
    (net (code "6") (name "/CANH") (class "Default")
      (node (ref "J1") (pin "1") (pinfunction "1_1") (pintype "passive"))
      (node (ref "J2") (pin "1") (pinfunction "1_1") (pintype "passive"))
      (node (ref "U7") (pin "7") (pinfunction "CANH_7") (pintype "bidirectional"))
      (node (ref "U7B") (pin "7") (pinfunction "CANH_7") (pintype "bidirectional"))
    )
    (net (code "7") (name "/CANL") (class "Default")
      (node (ref "J1") (pin "2") (pinfunction "2_2") (pintype "passive"))
      (node (ref "J2") (pin "2") (pinfunction "2_2") (pintype "passive"))
      (node (ref "U7") (pin "6") (pinfunction "CANL_6") (pintype "bidirectional"))
      (node (ref "U7B") (pin "6") (pinfunction "CANL_6") (pintype "bidirectional"))
    )
    (net (code "8") (name "/GND4") (class "Default")
      (node (ref "U$1") (pin "GND4") (pinfunction "GND4_GND4") (pintype "power_in"))
    )
    (net (code "9") (name "/PWR_POS") (class "Default")
      (node (ref "J1") (pin "8") (pinfunction "8_8") (pintype "passive"))
      (node (ref "J2") (pin "8") (pinfunction "8_8") (pintype "passive"))
      (node (ref "R40") (pin "2") (pinfunction "2_2") (pintype "passive"))
    )
    (net (code "10") (name "/U5V") (class "Default")
      (node (ref "U$1") (pin "U5V") (pinfunction "U5V_U5V") (pintype "power_in"))
    )
    (net (code "11") (name "/VBAT") (class "Default")
      (node (ref "U$1") (pin "VBAT") (pinfunction "VBAT_VBAT") (pintype "power_in"))
    )
    (net (code "12") (name "/VDD") (class "Default")
      (node (ref "U$1") (pin "VDD") (pinfunction "VDD_VDD") (pintype "power_in"))
    )
    (net (code "13") (name "CANRX") (class "Default")
      (node (ref "U$1") (pin "PB8") (pinfunction "PB8_PB8") (pintype "bidirectional"))
      (node (ref "U7") (pin "4") (pinfunction "RXD_4") (pintype "output"))
      (node (ref "U7B") (pin "4") (pinfunction "RXD_4") (pintype "bidirectional"))
    )
    (net (code "14") (name "CANTX") (class "Default")
      (node (ref "U$1") (pin "PB9") (pinfunction "PB9_PB9") (pintype "bidirectional"))
      (node (ref "U7") (pin "1") (pinfunction "TXD_1") (pintype "input"))
      (node (ref "U7B") (pin "1") (pinfunction "TXD_1") (pintype "bidirectional"))
    )
    (net (code "15") (name "E_CS") (class "Default")
      (node (ref "JP2") (pin "4") (pinfunction "4_4") (pintype "passive"))
      (node (ref "R23") (pin "2") (pinfunction "2_2") (pintype "passive"))
      (node (ref "U$1") (pin "PC10") (pinfunction "PC10_PC10") (pintype "bidirectional"))
    )
    (net (code "16") (name "E_LAT") (class "Default")
      (node (ref "JP2") (pin "5") (pinfunction "5_5") (pintype "passive"))
      (node (ref "R22") (pin "2") (pinfunction "2_2") (pintype "passive"))
      (node (ref "U$1") (pin "PC11") (pinfunction "PC11_PC11") (pintype "bidirectional"))
    )
    (net (code "17") (name "GND") (class "Default")
      (node (ref "C1") (pin "2") (pinfunction "2_2") (pintype "passive"))
      (node (ref "C10") (pin "2") (pinfunction "2_2") (pintype "passive"))
      (node (ref "C11") (pin "2") (pinfunction "2_2") (pintype "passive"))
      (node (ref "C2") (pin "-") (pinfunction "-_-") (pintype "passive"))
      (node (ref "C3") (pin "2") (pinfunction "2_2") (pintype "passive"))
      (node (ref "C4") (pin "2") (pinfunction "2_2") (pintype "passive"))
      (node (ref "C5") (pin "2") (pinfunction "2_2") (pintype "passive"))
      (node (ref "C6") (pin "2") (pinfunction "2_2") (pintype "passive"))
      (node (ref "C7") (pin "2") (pinfunction "2_2") (pintype "passive"))
      (node (ref "C8") (pin "2") (pinfunction "2_2") (pintype "passive"))
      (node (ref "C9") (pin "2") (pinfunction "2_2") (pintype "passive"))
      (node (ref "D1") (pin "A") (pinfunction "A_A") (pintype "passive"))
      (node (ref "D3") (pin "A") (pinfunction "A_A") (pintype "passive"))
      (node (ref "J1") (pin "3") (pinfunction "3_3") (pintype "passive"))
      (node (ref "J1") (pin "6") (pinfunction "6_6") (pintype "passive"))
      (node (ref "J1") (pin "7") (pinfunction "7_7") (pintype "passive"))
      (node (ref "J2") (pin "3") (pinfunction "3_3") (pintype "passive"))
      (node (ref "J2") (pin "6") (pinfunction "6_6") (pintype "passive"))
      (node (ref "J2") (pin "7") (pinfunction "7_7") (pintype "passive"))
      (node (ref "J3") (pin "2") (pinfunction "2_2") (pintype "passive"))
      (node (ref "J3") (pin "3") (pinfunction "3_3") (pintype "passive"))
      (node (ref "JP1") (pin "4") (pinfunction "4_4") (pintype "passive"))
      (node (ref "JP2") (pin "8") (pinfunction "8_8") (pintype "passive"))
      (node (ref "JP5") (pin "5") (pinfunction "5_5") (pintype "passive"))
      (node (ref "JP5") (pin "6") (pinfunction "6_6") (pintype "passive"))
      (node (ref "JP6") (pin "5") (pinfunction "5_5") (pintype "passive"))
      (node (ref "JP6") (pin "6") (pinfunction "6_6") (pintype "passive"))
      (node (ref "JP7") (pin "5") (pinfunction "5_5") (pintype "passive"))
      (node (ref "JP7") (pin "6") (pinfunction "6_6") (pintype "passive"))
      (node (ref "JP8") (pin "5") (pinfunction "5_5") (pintype "passive"))
      (node (ref "JP8") (pin "6") (pinfunction "6_6") (pintype "passive"))
      (node (ref "PORTA") (pin "5") (pinfunction "5_5") (pintype "passive"))
      (node (ref "PORTB") (pin "5") (pinfunction "5_5") (pintype "passive"))
      (node (ref "PORTC") (pin "5") (pinfunction "5_5") (pintype "passive"))
      (node (ref "Q1") (pin "2") (pinfunction "S_2") (pintype "passive"))
      (node (ref "Q10") (pin "2") (pinfunction "S_2") (pintype "passive"))
      (node (ref "Q11") (pin "2") (pinfunction "S_2") (pintype "passive"))
      (node (ref "Q12") (pin "2") (pinfunction "S_2") (pintype "passive"))
      (node (ref "Q13") (pin "2") (pinfunction "S_2") (pintype "passive"))
      (node (ref "Q14") (pin "2") (pinfunction "S_2") (pintype "passive"))
      (node (ref "Q15") (pin "2") (pinfunction "S_2") (pintype "passive"))
      (node (ref "Q16") (pin "2") (pinfunction "S_2") (pintype "passive"))
      (node (ref "Q2") (pin "2") (pinfunction "S_2") (pintype "passive"))
      (node (ref "Q3") (pin "2") (pinfunction "S_2") (pintype "passive"))
      (node (ref "Q4") (pin "2") (pinfunction "S_2") (pintype "passive"))
      (node (ref "Q5") (pin "2") (pinfunction "S_2") (pintype "passive"))
      (node (ref "Q6") (pin "2") (pinfunction "S_2") (pintype "passive"))
      (node (ref "Q7") (pin "2") (pinfunction "S_2") (pintype "passive"))
      (node (ref "Q8") (pin "2") (pinfunction "S_2") (pintype "passive"))
      (node (ref "Q9") (pin "2") (pinfunction "S_2") (pintype "passive"))
      (node (ref "R2") (pin "1") (pinfunction "1_1") (pintype "passive"))
      (node (ref "R61") (pin "2") (pinfunction "2_2") (pintype "passive"))
      (node (ref "SJ12") (pin "P$2") (pinfunction "2_P$2") (pintype "passive"))
      (node (ref "SJ3") (pin "2") (pinfunction "2_2") (pintype "passive"))
      (node (ref "SJ6") (pin "P$2") (pinfunction "2_P$2") (pintype "passive"))
      (node (ref "SJ9") (pin "2") (pinfunction "2_2") (pintype "passive"))
      (node (ref "U$1") (pin "GND3") (pinfunction "GND3_GND3") (pintype "power_in"))
      (node (ref "U$1") (pin "GND5") (pinfunction "GND5_GND5") (pintype "power_in"))
      (node (ref "U$1") (pin "GND6") (pinfunction "GND6_GND6") (pintype "power_in"))
      (node (ref "U$1") (pin "GND7") (pinfunction "GND7_GND7") (pintype "power_in"))
      (node (ref "U$1") (pin "GND8") (pinfunction "GND8_GND8") (pintype "power_in"))
      (node (ref "U1") (pin "6") (pinfunction "INH_6") (pintype "input"))
      (node (ref "U1") (pin "8") (pinfunction "GND_8") (pintype "power_in"))
      (node (ref "U10") (pin "11") (pinfunction "V-_11") (pintype "power_in"))
      (node (ref "U11") (pin "13") (pinfunction "G_13") (pintype "input"))
      (node (ref "U11") (pin "8") (pinfunction "GND_8") (pintype "power_in"))
      (node (ref "U13") (pin "13") (pinfunction "G_13") (pintype "input"))
      (node (ref "U13") (pin "8") (pinfunction "GND_8") (pintype "power_in"))
      (node (ref "U2") (pin "6") (pinfunction "INH_6") (pintype "input"))
      (node (ref "U2") (pin "8") (pinfunction "GND_8") (pintype "power_in"))
      (node (ref "U3") (pin "3") (pinfunction "VSS_3") (pintype "power_in"))
      (node (ref "U4") (pin "3") (pinfunction "VSS_3") (pintype "power_in"))
      (node (ref "U5") (pin "3") (pinfunction "VSS_3") (pintype "power_in"))
      (node (ref "U6") (pin "3") (pinfunction "VSS_3") (pintype "power_in"))
      (node (ref "U7") (pin "2") (pinfunction "GND_2") (pintype "power_in"))
      (node (ref "U7B") (pin "2") (pinfunction "VSS_2") (pintype "power_in"))
      (node (ref "U8") (pin "4") (pinfunction "SD_4") (pintype "bidirectional"))
      (node (ref "U8") (pin "5") (pinfunction "GND1_5") (pintype "power_in"))
      (node (ref "U8") (pin "6") (pinfunction "GND2_6") (pintype "power_in"))
      (node (ref "U8") (pin "7") (pinfunction "GND3_7") (pintype "power_in"))
      (node (ref "U8") (pin "8") (pinfunction "GND4_8") (pintype "power_in"))
      (node (ref "U8B") (pin "2") (pinfunction "GNDSIG_2") (pintype "input"))
      (node (ref "U8B") (pin "3") (pinfunction "~{ON/OFF}_3") (pintype "input"))
      (node (ref "U8B") (pin "4") (pinfunction "GND_4") (pintype "power_in"))
      (node (ref "U9") (pin "11") (pinfunction "V-_11") (pintype "power_in"))
      (node (ref "X6") (pin "2") (pinfunction "2_2") (pintype "passive"))
    )
    (net (code "18") (name "I2CSCL") (class "Default")
      (node (ref "JP1") (pin "1") (pinfunction "1_1") (pintype "passive"))
      (node (ref "R62") (pin "2") (pinfunction "2_2") (pintype "passive"))
      (node (ref "U$1") (pin "PB6") (pinfunction "PB6_PB6") (pintype "bidirectional"))
    )
    (net (code "19") (name "I2CSDA") (class "Default")
      (node (ref "JP1") (pin "2") (pinfunction "2_2") (pintype "passive"))
      (node (ref "R63") (pin "2") (pinfunction "2_2") (pintype "passive"))
      (node (ref "U$1") (pin "PB7") (pinfunction "PB7_PB7") (pintype "bidirectional"))
    )
    (net (code "20") (name "ILAT") (class "Default")
      (node (ref "U$1") (pin "PA6") (pinfunction "PA6_PA6") (pintype "bidirectional"))
      (node (ref "U1") (pin "15") (pinfunction "SH/~{LD}_15") (pintype "input"))
      (node (ref "U2") (pin "15") (pinfunction "SH/~{LD}_15") (pintype "input"))
    )
    (net (code "21") (name "MISO") (class "Default")
      (node (ref "JP2") (pin "1") (pinfunction "1_1") (pintype "passive"))
      (node (ref "U$1") (pin "PB4") (pinfunction "PB4_PB4") (pintype "bidirectional"))
    )
    (net (code "22") (name "MISO2") (class "Default")
      (node (ref "SJ13") (pin "P$2") (pinfunction "2_P$2") (pintype "passive"))
      (node (ref "SJ19") (pin "P$2") (pinfunction "2_P$2") (pintype "passive"))
      (node (ref "U$1") (pin "PC2") (pinfunction "PC2_PC2") (pintype "bidirectional"))
      (node (ref "U2") (pin "13") (pinfunction "QH_13") (pintype "output"))
    )
    (net (code "23") (name "MOSI") (class "Default")
      (node (ref "R20") (pin "1") (pinfunction "1_1") (pintype "passive"))
      (node (ref "SJ15") (pin "1") (pinfunction "1_1") (pintype "passive"))
      (node (ref "SJ17") (pin "P$2") (pinfunction "2_P$2") (pintype "passive"))
      (node (ref "U$1") (pin "PB5") (pinfunction "PB5_PB5") (pintype "bidirectional"))
      (node (ref "U11") (pin "14") (pinfunction "SER_14") (pintype "input"))
    )
    (net (code "24") (name "Net-(D2-PadA)") (class "Default")
      (node (ref "D2") (pin "A") (pinfunction "A_A") (pintype "passive"))
      (node (ref "D4") (pin "A") (pinfunction "A_A") (pintype "passive"))
      (node (ref "JP4") (pin "4") (pinfunction "4_4") (pintype "passive"))
    )
    (net (code "25") (name "Net-(D2-PadC)") (class "Default")
      (node (ref "D2") (pin "C") (pinfunction "C_C") (pintype "passive"))
      (node (ref "D4") (pin "C") (pinfunction "C_C") (pintype "passive"))
      (node (ref "JP4") (pin "1") (pinfunction "1_1") (pintype "passive"))
    )
    (net (code "26") (name "Net-(J1-Pad4)") (class "Default")
      (node (ref "J1") (pin "4") (pinfunction "4_4") (pintype "passive"))
      (node (ref "J2") (pin "4") (pinfunction "4_4") (pintype "passive"))
    )
    (net (code "27") (name "Net-(J1-Pad5)") (class "Default")
      (node (ref "J1") (pin "5") (pinfunction "5_5") (pintype "passive"))
      (node (ref "J2") (pin "5") (pinfunction "5_5") (pintype "passive"))
    )
    (net (code "28") (name "Net-(JP4-Pad3)") (class "Default")
      (node (ref "JP4") (pin "3") (pinfunction "3_3") (pintype "passive"))
      (node (ref "R40") (pin "1") (pinfunction "1_1") (pintype "passive"))
    )
    (net (code "29") (name "Net-(PORTA-Pad1)") (class "Default")
      (node (ref "PORTA") (pin "1") (pinfunction "1_1") (pintype "passive"))
      (node (ref "R44") (pin "2") (pinfunction "2_2") (pintype "passive"))
      (node (ref "R53") (pin "2") (pinfunction "2_2") (pintype "passive"))
      (node (ref "RN3") (pin "1") (pinfunction "1_1") (pintype "passive"))
      (node (ref "RN4") (pin "9") (pinfunction "9_9") (pintype "passive"))
      (node (ref "X1") (pin "1") (pinfunction "1_1") (pintype "passive"))
    )
    (net (code "30") (name "Net-(PORTB-Pad1)") (class "Default")
      (node (ref "PORTB") (pin "1") (pinfunction "1_1") (pintype "passive"))
      (node (ref "R35") (pin "2") (pinfunction "2_2") (pintype "passive"))
      (node (ref "R45") (pin "2") (pinfunction "2_2") (pintype "passive"))
      (node (ref "RN1") (pin "1") (pinfunction "1_1") (pintype "passive"))
      (node (ref "RN2") (pin "9") (pinfunction "9_9") (pintype "passive"))
      (node (ref "X2") (pin "1") (pinfunction "1_1") (pintype "passive"))
    )
    (net (code "31") (name "Net-(Q1-D)") (class "Default")
      (node (ref "Q1") (pin "3") (pinfunction "D_3") (pintype "passive"))
      (node (ref "U12") (pin "18") (pinfunction "O1_18") (pintype "open_collector"))
      (node (ref "X5") (pin "1") (pinfunction "1_1") (pintype "passive"))
    )
    (net (code "32") (name "Net-(Q1-G)") (class "Default")
      (node (ref "Q1") (pin "1") (pinfunction "G_1") (pintype "passive"))
      (node (ref "R3") (pin "2") (pinfunction "2_2") (pintype "passive"))
    )
    (net (code "33") (name "Net-(Q2-D)") (class "Default")
      (node (ref "Q2") (pin "3") (pinfunction "D_3") (pintype "passive"))
      (node (ref "U12") (pin "17") (pinfunction "O2_17") (pintype "open_collector"))
      (node (ref "X5") (pin "2") (pinfunction "2_2") (pintype "passive"))
    )
    (net (code "34") (name "Net-(Q2-G)") (class "Default")
      (node (ref "Q2") (pin "1") (pinfunction "G_1") (pintype "passive"))
      (node (ref "R4") (pin "2") (pinfunction "2_2") (pintype "passive"))
    )
    (net (code "35") (name "Net-(Q3-D)") (class "Default")
      (node (ref "Q3") (pin "3") (pinfunction "D_3") (pintype "passive"))
      (node (ref "U12") (pin "16") (pinfunction "O3_16") (pintype "open_collector"))
      (node (ref "X5") (pin "3") (pinfunction "3_3") (pintype "passive"))
    )
    (net (code "36") (name "Net-(Q3-G)") (class "Default")
      (node (ref "Q3") (pin "1") (pinfunction "G_1") (pintype "passive"))
      (node (ref "R5") (pin "2") (pinfunction "2_2") (pintype "passive"))
    )
    (net (code "37") (name "Net-(Q4-D)") (class "Default")
      (node (ref "Q4") (pin "3") (pinfunction "D_3") (pintype "passive"))
      (node (ref "U12") (pin "15") (pinfunction "O4_15") (pintype "open_collector"))
      (node (ref "X5") (pin "4") (pinfunction "4_4") (pintype "passive"))
    )
    (net (code "38") (name "Net-(Q4-G)") (class "Default")
      (node (ref "Q4") (pin "1") (pinfunction "G_1") (pintype "passive"))
      (node (ref "R6") (pin "2") (pinfunction "2_2") (pintype "passive"))
    )
    (net (code "39") (name "Net-(Q5-D)") (class "Default")
      (node (ref "Q5") (pin "3") (pinfunction "D_3") (pintype "passive"))
      (node (ref "U12") (pin "14") (pinfunction "O5_14") (pintype "open_collector"))
      (node (ref "X5") (pin "5") (pinfunction "5_5") (pintype "passive"))
    )
    (net (code "40") (name "Net-(Q5-G)") (class "Default")
      (node (ref "Q5") (pin "1") (pinfunction "G_1") (pintype "passive"))
      (node (ref "R7") (pin "2") (pinfunction "2_2") (pintype "passive"))
    )
    (net (code "41") (name "Net-(Q6-D)") (class "Default")
      (node (ref "Q6") (pin "3") (pinfunction "D_3") (pintype "passive"))
      (node (ref "U12") (pin "13") (pinfunction "O6_13") (pintype "open_collector"))
      (node (ref "X5") (pin "6") (pinfunction "6_6") (pintype "passive"))
    )
    (net (code "42") (name "Net-(Q6-G)") (class "Default")
      (node (ref "Q6") (pin "1") (pinfunction "G_1") (pintype "passive"))
      (node (ref "R8") (pin "2") (pinfunction "2_2") (pintype "passive"))
    )
    (net (code "43") (name "Net-(Q7-D)") (class "Default")
      (node (ref "Q7") (pin "3") (pinfunction "D_3") (pintype "passive"))
      (node (ref "U12") (pin "12") (pinfunction "O7_12") (pintype "open_collector"))
      (node (ref "X5") (pin "7") (pinfunction "7_7") (pintype "passive"))
    )
    (net (code "44") (name "Net-(Q7-G)") (class "Default")
      (node (ref "Q7") (pin "1") (pinfunction "G_1") (pintype "passive"))
      (node (ref "R9") (pin "2") (pinfunction "2_2") (pintype "passive"))
    )
    (net (code "45") (name "Net-(Q8-D)") (class "Default")
      (node (ref "Q8") (pin "3") (pinfunction "D_3") (pintype "passive"))
      (node (ref "U12") (pin "11") (pinfunction "O8_11") (pintype "open_collector"))
      (node (ref "X5") (pin "8") (pinfunction "8_8") (pintype "passive"))
    )
    (net (code "46") (name "Net-(Q8-G)") (class "Default")
      (node (ref "Q8") (pin "1") (pinfunction "G_1") (pintype "passive"))
      (node (ref "R10") (pin "2") (pinfunction "2_2") (pintype "passive"))
    )
    (net (code "47") (name "Net-(Q9-D)") (class "Default")
      (node (ref "Q9") (pin "3") (pinfunction "D_3") (pintype "passive"))
      (node (ref "U14") (pin "18") (pinfunction "O1_18") (pintype "open_collector"))
      (node (ref "X4") (pin "1") (pinfunction "1_1") (pintype "passive"))
    )
    (net (code "48") (name "Net-(Q9-G)") (class "Default")
      (node (ref "Q9") (pin "1") (pinfunction "G_1") (pintype "passive"))
      (node (ref "R11") (pin "2") (pinfunction "2_2") (pintype "passive"))
    )
    (net (code "49") (name "Net-(Q10-D)") (class "Default")
      (node (ref "Q10") (pin "3") (pinfunction "D_3") (pintype "passive"))
      (node (ref "U14") (pin "17") (pinfunction "O2_17") (pintype "open_collector"))
      (node (ref "X4") (pin "2") (pinfunction "2_2") (pintype "passive"))
    )
    (net (code "50") (name "Net-(Q10-G)") (class "Default")
      (node (ref "Q10") (pin "1") (pinfunction "G_1") (pintype "passive"))
      (node (ref "R12") (pin "2") (pinfunction "2_2") (pintype "passive"))
    )
    (net (code "51") (name "Net-(Q11-D)") (class "Default")
      (node (ref "Q11") (pin "3") (pinfunction "D_3") (pintype "passive"))
      (node (ref "U14") (pin "16") (pinfunction "O3_16") (pintype "open_collector"))
      (node (ref "X4") (pin "3") (pinfunction "3_3") (pintype "passive"))
    )
    (net (code "52") (name "Net-(Q11-G)") (class "Default")
      (node (ref "Q11") (pin "1") (pinfunction "G_1") (pintype "passive"))
      (node (ref "R13") (pin "2") (pinfunction "2_2") (pintype "passive"))
    )
    (net (code "53") (name "Net-(Q12-D)") (class "Default")
      (node (ref "Q12") (pin "3") (pinfunction "D_3") (pintype "passive"))
      (node (ref "U14") (pin "15") (pinfunction "O4_15") (pintype "open_collector"))
      (node (ref "X4") (pin "4") (pinfunction "4_4") (pintype "passive"))
    )
    (net (code "54") (name "Net-(Q12-G)") (class "Default")
      (node (ref "Q12") (pin "1") (pinfunction "G_1") (pintype "passive"))
      (node (ref "R14") (pin "2") (pinfunction "2_2") (pintype "passive"))
    )
    (net (code "55") (name "Net-(Q13-D)") (class "Default")
      (node (ref "Q13") (pin "3") (pinfunction "D_3") (pintype "passive"))
      (node (ref "U14") (pin "14") (pinfunction "O5_14") (pintype "open_collector"))
      (node (ref "X4") (pin "5") (pinfunction "5_5") (pintype "passive"))
    )
    (net (code "56") (name "Net-(Q13-G)") (class "Default")
      (node (ref "Q13") (pin "1") (pinfunction "G_1") (pintype "passive"))
      (node (ref "R15") (pin "2") (pinfunction "2_2") (pintype "passive"))
    )
    (net (code "57") (name "Net-(Q14-D)") (class "Default")
      (node (ref "Q14") (pin "3") (pinfunction "D_3") (pintype "passive"))
      (node (ref "U14") (pin "13") (pinfunction "O6_13") (pintype "open_collector"))
      (node (ref "X4") (pin "6") (pinfunction "6_6") (pintype "passive"))
    )
    (net (code "58") (name "Net-(Q14-G)") (class "Default")
      (node (ref "Q14") (pin "1") (pinfunction "G_1") (pintype "passive"))
      (node (ref "R16") (pin "2") (pinfunction "2_2") (pintype "passive"))
    )
    (net (code "59") (name "Net-(Q15-D)") (class "Default")
      (node (ref "Q15") (pin "3") (pinfunction "D_3") (pintype "passive"))
      (node (ref "U14") (pin "12") (pinfunction "O7_12") (pintype "open_collector"))
      (node (ref "X4") (pin "7") (pinfunction "7_7") (pintype "passive"))
    )
    (net (code "60") (name "Net-(Q15-G)") (class "Default")
      (node (ref "Q15") (pin "1") (pinfunction "G_1") (pintype "passive"))
      (node (ref "R17") (pin "2") (pinfunction "2_2") (pintype "passive"))
    )
    (net (code "61") (name "Net-(Q16-D)") (class "Default")
      (node (ref "Q16") (pin "3") (pinfunction "D_3") (pintype "passive"))
      (node (ref "U14") (pin "11") (pinfunction "O8_11") (pintype "open_collector"))
      (node (ref "X4") (pin "8") (pinfunction "8_8") (pintype "passive"))
    )
    (net (code "62") (name "Net-(Q16-G)") (class "Default")
      (node (ref "Q16") (pin "1") (pinfunction "G_1") (pintype "passive"))
      (node (ref "R18") (pin "2") (pinfunction "2_2") (pintype "passive"))
    )
    (net (code "63") (name "Net-(RN1A-2)") (class "Default")
      (node (ref "R35") (pin "1") (pinfunction "1_1") (pintype "passive"))
      (node (ref "RN1") (pin "16") (pinfunction "2_16") (pintype "passive"))
      (node (ref "U2") (pin "14") (pinfunction "H_14") (pintype "input"))
    )
    (net (code "64") (name "Net-(RN1B-1)") (class "Default")
      (node (ref "PORTB") (pin "2") (pinfunction "2_2") (pintype "passive"))
      (node (ref "R34") (pin "2") (pinfunction "2_2") (pintype "passive"))
      (node (ref "R46") (pin "2") (pinfunction "2_2") (pintype "passive"))
      (node (ref "RN1") (pin "2") (pinfunction "1_2") (pintype "passive"))
      (node (ref "RN2") (pin "8") (pinfunction "8_8") (pintype "passive"))
      (node (ref "X2") (pin "2") (pinfunction "2_2") (pintype "passive"))
    )
    (net (code "65") (name "Net-(RN1B-2)") (class "Default")
      (node (ref "R34") (pin "1") (pinfunction "1_1") (pintype "passive"))
      (node (ref "RN1") (pin "15") (pinfunction "2_15") (pintype "passive"))
      (node (ref "U2") (pin "12") (pinfunction "G_12") (pintype "input"))
    )
    (net (code "66") (name "Net-(RN1C-1)") (class "Default")
      (node (ref "PORTB") (pin "3") (pinfunction "3_3") (pintype "passive"))
      (node (ref "R33") (pin "2") (pinfunction "2_2") (pintype "passive"))
      (node (ref "R47") (pin "2") (pinfunction "2_2") (pintype "passive"))
      (node (ref "RN1") (pin "3") (pinfunction "1_3") (pintype "passive"))
      (node (ref "RN2") (pin "7") (pinfunction "7_7") (pintype "passive"))
      (node (ref "X2") (pin "3") (pinfunction "3_3") (pintype "passive"))
    )
    (net (code "67") (name "Net-(RN1C-2)") (class "Default")
      (node (ref "R33") (pin "1") (pinfunction "1_1") (pintype "passive"))
      (node (ref "RN1") (pin "14") (pinfunction "2_14") (pintype "passive"))
      (node (ref "U2") (pin "11") (pinfunction "F_11") (pintype "input"))
    )
    (net (code "68") (name "Net-(RN1D-1)") (class "Default")
      (node (ref "PORTB") (pin "4") (pinfunction "4_4") (pintype "passive"))
      (node (ref "R32") (pin "2") (pinfunction "2_2") (pintype "passive"))
      (node (ref "R48") (pin "2") (pinfunction "2_2") (pintype "passive"))
      (node (ref "RN1") (pin "4") (pinfunction "1_4") (pintype "passive"))
      (node (ref "RN2") (pin "6") (pinfunction "6_6") (pintype "passive"))
      (node (ref "X2") (pin "4") (pinfunction "4_4") (pintype "passive"))
    )
    (net (code "69") (name "Net-(RN1D-2)") (class "Default")
      (node (ref "R32") (pin "1") (pinfunction "1_1") (pintype "passive"))
      (node (ref "RN1") (pin "13") (pinfunction "2_13") (pintype "passive"))
      (node (ref "U2") (pin "10") (pinfunction "E_10") (pintype "input"))
    )
    (net (code "70") (name "Net-(RN1E-1)") (class "Default")
      (node (ref "PORTB") (pin "7") (pinfunction "7_7") (pintype "passive"))
      (node (ref "R31") (pin "2") (pinfunction "2_2") (pintype "passive"))
      (node (ref "R49") (pin "2") (pinfunction "2_2") (pintype "passive"))
      (node (ref "RN1") (pin "5") (pinfunction "1_5") (pintype "passive"))
      (node (ref "RN2") (pin "5") (pinfunction "5_5") (pintype "passive"))
      (node (ref "X2") (pin "5") (pinfunction "5_5") (pintype "passive"))
    )
    (net (code "71") (name "Net-(RN1E-2)") (class "Default")
      (node (ref "R31") (pin "1") (pinfunction "1_1") (pintype "passive"))
      (node (ref "RN1") (pin "12") (pinfunction "2_12") (pintype "passive"))
      (node (ref "U2") (pin "5") (pinfunction "D_5") (pintype "input"))
    )
    (net (code "72") (name "Net-(RN1F-1)") (class "Default")
      (node (ref "PORTB") (pin "8") (pinfunction "8_8") (pintype "passive"))
      (node (ref "R30") (pin "2") (pinfunction "2_2") (pintype "passive"))
      (node (ref "R50") (pin "2") (pinfunction "2_2") (pintype "passive"))
      (node (ref "RN1") (pin "6") (pinfunction "1_6") (pintype "passive"))
      (node (ref "RN2") (pin "4") (pinfunction "4_4") (pintype "passive"))
      (node (ref "X2") (pin "6") (pinfunction "6_6") (pintype "passive"))
    )
    (net (code "73") (name "Net-(RN1F-2)") (class "Default")
      (node (ref "R30") (pin "1") (pinfunction "1_1") (pintype "passive"))
      (node (ref "RN1") (pin "11") (pinfunction "2_11") (pintype "passive"))
      (node (ref "U2") (pin "4") (pinfunction "C_4") (pintype "input"))
    )
    (net (code "74") (name "Net-(RN1G-1)") (class "Default")
      (node (ref "PORTB") (pin "9") (pinfunction "9_9") (pintype "passive"))
      (node (ref "R29") (pin "2") (pinfunction "2_2") (pintype "passive"))
      (node (ref "R51") (pin "2") (pinfunction "2_2") (pintype "passive"))
      (node (ref "RN1") (pin "7") (pinfunction "1_7") (pintype "passive"))
      (node (ref "RN2") (pin "3") (pinfunction "3_3") (pintype "passive"))
      (node (ref "X2") (pin "7") (pinfunction "7_7") (pintype "passive"))
    )
    (net (code "75") (name "Net-(RN1G-2)") (class "Default")
      (node (ref "R29") (pin "1") (pinfunction "1_1") (pintype "passive"))
      (node (ref "RN1") (pin "10") (pinfunction "2_10") (pintype "passive"))
      (node (ref "U2") (pin "3") (pinfunction "B_3") (pintype "input"))
    )
    (net (code "76") (name "Net-(RN1H-1)") (class "Default")
      (node (ref "PORTB") (pin "10") (pinfunction "10_10") (pintype "passive"))
      (node (ref "R28") (pin "2") (pinfunction "2_2") (pintype "passive"))
      (node (ref "R52") (pin "2") (pinfunction "2_2") (pintype "passive"))
      (node (ref "RN1") (pin "8") (pinfunction "1_8") (pintype "passive"))
      (node (ref "RN2") (pin "2") (pinfunction "2_2") (pintype "passive"))
      (node (ref "X2") (pin "8") (pinfunction "8_8") (pintype "passive"))
    )
    (net (code "77") (name "Net-(RN1H-2)") (class "Default")
      (node (ref "R28") (pin "1") (pinfunction "1_1") (pintype "passive"))
      (node (ref "RN1") (pin "9") (pinfunction "2_9") (pintype "passive"))
      (node (ref "U2") (pin "2") (pinfunction "A_2") (pintype "input"))
    )
    (net (code "78") (name "Net-(RN3A-2)") (class "Default")
      (node (ref "R44") (pin "1") (pinfunction "1_1") (pintype "passive"))
      (node (ref "RN3") (pin "16") (pinfunction "2_16") (pintype "passive"))
      (node (ref "U1") (pin "14") (pinfunction "H_14") (pintype "input"))
    )
    (net (code "79") (name "Net-(RN3B-1)") (class "Default")
      (node (ref "PORTA") (pin "2") (pinfunction "2_2") (pintype "passive"))
      (node (ref "R43") (pin "2") (pinfunction "2_2") (pintype "passive"))
      (node (ref "R54") (pin "2") (pinfunction "2_2") (pintype "passive"))
      (node (ref "RN3") (pin "2") (pinfunction "1_2") (pintype "passive"))
      (node (ref "RN4") (pin "8") (pinfunction "8_8") (pintype "passive"))
      (node (ref "X1") (pin "2") (pinfunction "2_2") (pintype "passive"))
    )
    (net (code "80") (name "Net-(RN3B-2)") (class "Default")
      (node (ref "R43") (pin "1") (pinfunction "1_1") (pintype "passive"))
      (node (ref "RN3") (pin "15") (pinfunction "2_15") (pintype "passive"))
      (node (ref "U1") (pin "12") (pinfunction "G_12") (pintype "input"))
    )
    (net (code "81") (name "Net-(RN3C-1)") (class "Default")
      (node (ref "PORTA") (pin "3") (pinfunction "3_3") (pintype "passive"))
      (node (ref "R42") (pin "2") (pinfunction "2_2") (pintype "passive"))
      (node (ref "R55") (pin "2") (pinfunction "2_2") (pintype "passive"))
      (node (ref "RN3") (pin "3") (pinfunction "1_3") (pintype "passive"))
      (node (ref "RN4") (pin "7") (pinfunction "7_7") (pintype "passive"))
      (node (ref "X1") (pin "3") (pinfunction "3_3") (pintype "passive"))
    )
    (net (code "82") (name "Net-(RN3C-2)") (class "Default")
      (node (ref "R42") (pin "1") (pinfunction "1_1") (pintype "passive"))
      (node (ref "RN3") (pin "14") (pinfunction "2_14") (pintype "passive"))
      (node (ref "U1") (pin "11") (pinfunction "F_11") (pintype "input"))
    )
    (net (code "83") (name "Net-(RN3D-1)") (class "Default")
      (node (ref "PORTA") (pin "4") (pinfunction "4_4") (pintype "passive"))
      (node (ref "R41") (pin "2") (pinfunction "2_2") (pintype "passive"))
      (node (ref "R56") (pin "2") (pinfunction "2_2") (pintype "passive"))
      (node (ref "RN3") (pin "4") (pinfunction "1_4") (pintype "passive"))
      (node (ref "RN4") (pin "6") (pinfunction "6_6") (pintype "passive"))
      (node (ref "X1") (pin "4") (pinfunction "4_4") (pintype "passive"))
    )
    (net (code "84") (name "Net-(RN3D-2)") (class "Default")
      (node (ref "R41") (pin "1") (pinfunction "1_1") (pintype "passive"))
      (node (ref "RN3") (pin "13") (pinfunction "2_13") (pintype "passive"))
      (node (ref "U1") (pin "10") (pinfunction "E_10") (pintype "input"))
    )
    (net (code "85") (name "Net-(RN3E-1)") (class "Default")
      (node (ref "PORTA") (pin "7") (pinfunction "7_7") (pintype "passive"))
      (node (ref "R39") (pin "2") (pinfunction "2_2") (pintype "passive"))
      (node (ref "R57") (pin "2") (pinfunction "2_2") (pintype "passive"))
      (node (ref "RN3") (pin "5") (pinfunction "1_5") (pintype "passive"))
      (node (ref "RN4") (pin "5") (pinfunction "5_5") (pintype "passive"))
      (node (ref "X1") (pin "5") (pinfunction "5_5") (pintype "passive"))
    )
    (net (code "86") (name "Net-(RN3E-2)") (class "Default")
      (node (ref "R39") (pin "1") (pinfunction "1_1") (pintype "passive"))
      (node (ref "RN3") (pin "12") (pinfunction "2_12") (pintype "passive"))
      (node (ref "U1") (pin "5") (pinfunction "D_5") (pintype "input"))
    )
    (net (code "87") (name "Net-(RN3F-1)") (class "Default")
      (node (ref "PORTA") (pin "8") (pinfunction "8_8") (pintype "passive"))
      (node (ref "R38") (pin "2") (pinfunction "2_2") (pintype "passive"))
      (node (ref "R58") (pin "2") (pinfunction "2_2") (pintype "passive"))
      (node (ref "RN3") (pin "6") (pinfunction "1_6") (pintype "passive"))
      (node (ref "RN4") (pin "4") (pinfunction "4_4") (pintype "passive"))
      (node (ref "X1") (pin "6") (pinfunction "6_6") (pintype "passive"))
    )
    (net (code "88") (name "Net-(RN3F-2)") (class "Default")
      (node (ref "R38") (pin "1") (pinfunction "1_1") (pintype "passive"))
      (node (ref "RN3") (pin "11") (pinfunction "2_11") (pintype "passive"))
      (node (ref "U1") (pin "4") (pinfunction "C_4") (pintype "input"))
    )
    (net (code "89") (name "Net-(RN3G-1)") (class "Default")
      (node (ref "PORTA") (pin "9") (pinfunction "9_9") (pintype "passive"))
      (node (ref "R37") (pin "2") (pinfunction "2_2") (pintype "passive"))
      (node (ref "R59") (pin "2") (pinfunction "2_2") (pintype "passive"))
      (node (ref "RN3") (pin "7") (pinfunction "1_7") (pintype "passive"))
      (node (ref "RN4") (pin "3") (pinfunction "3_3") (pintype "passive"))
      (node (ref "X1") (pin "7") (pinfunction "7_7") (pintype "passive"))
    )
    (net (code "90") (name "Net-(RN3G-2)") (class "Default")
      (node (ref "R37") (pin "1") (pinfunction "1_1") (pintype "passive"))
      (node (ref "RN3") (pin "10") (pinfunction "2_10") (pintype "passive"))
      (node (ref "U1") (pin "3") (pinfunction "B_3") (pintype "input"))
    )
    (net (code "91") (name "Net-(RN3H-1)") (class "Default")
      (node (ref "PORTA") (pin "10") (pinfunction "10_10") (pintype "passive"))
      (node (ref "R36") (pin "2") (pinfunction "2_2") (pintype "passive"))
      (node (ref "R60") (pin "2") (pinfunction "2_2") (pintype "passive"))
      (node (ref "RN3") (pin "8") (pinfunction "1_8") (pintype "passive"))
      (node (ref "RN4") (pin "2") (pinfunction "2_2") (pintype "passive"))
      (node (ref "X1") (pin "8") (pinfunction "8_8") (pintype "passive"))
    )
    (net (code "92") (name "Net-(RN3H-2)") (class "Default")
      (node (ref "R36") (pin "1") (pinfunction "1_1") (pintype "passive"))
      (node (ref "RN3") (pin "9") (pinfunction "2_9") (pintype "passive"))
      (node (ref "U1") (pin "2") (pinfunction "A_2") (pintype "input"))
    )
    (net (code "93") (name "Net-(SJ1-1)") (class "Default")
      (node (ref "SJ1") (pin "P$1") (pinfunction "1_P$1") (pintype "passive"))
      (node (ref "SJ2") (pin "P$1") (pinfunction "1_P$1") (pintype "passive"))
      (node (ref "SJ3") (pin "1") (pinfunction "1_1") (pintype "passive"))
      (node (ref "U12") (pin "9") (pinfunction "GND_9") (pintype "power_in"))
    )
    (net (code "94") (name "Net-(SJ4-1)") (class "Default")
      (node (ref "SJ4") (pin "P$1") (pinfunction "1_P$1") (pintype "passive"))
      (node (ref "SJ5") (pin "P$1") (pinfunction "1_P$1") (pintype "passive"))
      (node (ref "SJ6") (pin "P$1") (pinfunction "1_P$1") (pintype "passive"))
      (node (ref "U12") (pin "10") (pinfunction "CD+_10") (pintype "passive"))
    )
    (net (code "95") (name "Net-(SJ7-1)") (class "Default")
      (node (ref "SJ7") (pin "P$1") (pinfunction "1_P$1") (pintype "passive"))
      (node (ref "SJ8") (pin "P$1") (pinfunction "1_P$1") (pintype "passive"))
      (node (ref "SJ9") (pin "1") (pinfunction "1_1") (pintype "passive"))
      (node (ref "U14") (pin "9") (pinfunction "GND_9") (pintype "power_in"))
    )
    (net (code "96") (name "Net-(SJ10-1)") (class "Default")
      (node (ref "SJ10") (pin "P$1") (pinfunction "1_P$1") (pintype "passive"))
      (node (ref "SJ11") (pin "P$1") (pinfunction "1_P$1") (pintype "passive"))
      (node (ref "SJ12") (pin "P$1") (pinfunction "1_P$1") (pintype "passive"))
      (node (ref "U14") (pin "10") (pinfunction "CD+_10") (pintype "passive"))
    )
    (net (code "97") (name "Net-(SJ13-1)") (class "Default")
      (node (ref "SJ13") (pin "P$1") (pinfunction "1_P$1") (pintype "passive"))
      (node (ref "U$1") (pin "PB14") (pinfunction "PB14_PB14") (pintype "bidirectional"))
    )
    (net (code "98") (name "Net-(SJ14-1)") (class "Default")
      (node (ref "SJ14") (pin "P$1") (pinfunction "1_P$1") (pintype "passive"))
      (node (ref "U$1") (pin "VIN2") (pinfunction "VIN2_VIN2") (pintype "power_in"))
    )
    (net (code "99") (name "Net-(SJ16-2)") (class "Default")
      (node (ref "JP2") (pin "2") (pinfunction "2_2") (pintype "passive"))
      (node (ref "SJ15") (pin "2") (pinfunction "2_2") (pintype "passive"))
      (node (ref "SJ16") (pin "P$2") (pinfunction "2_P$2") (pintype "passive"))
    )
    (net (code "100") (name "Net-(SJ18-2)") (class "Default")
      (node (ref "SJ18") (pin "P$2") (pinfunction "2_P$2") (pintype "passive"))
      (node (ref "U7") (pin "5") (pinfunction "VREF_5") (pintype "output"))
      (node (ref "U7B") (pin "5") (pinfunction "VREF_5") (pintype "bidirectional"))
    )
    (net (code "101") (name "Net-(U3A-O)") (class "Default")
      (node (ref "PORTC") (pin "1") (pinfunction "1_1") (pintype "passive"))
      (node (ref "U3") (pin "7") (pinfunction "O_7") (pintype "output"))
      (node (ref "U9") (pin "7") (pinfunction "OUT_7") (pintype "output"))
      (node (ref "X3") (pin "1") (pinfunction "1_1") (pintype "passive"))
    )
    (net (code "102") (name "Net-(U3B-O)") (class "Default")
      (node (ref "PORTC") (pin "2") (pinfunction "2_2") (pintype "passive"))
      (node (ref "U3") (pin "5") (pinfunction "O_5") (pintype "output"))
      (node (ref "U9") (pin "8") (pinfunction "OUT_8") (pintype "output"))
      (node (ref "X3") (pin "2") (pinfunction "2_2") (pintype "passive"))
    )
    (net (code "103") (name "Net-(U4A-O)") (class "Default")
      (node (ref "PORTC") (pin "4") (pinfunction "4_4") (pintype "passive"))
      (node (ref "U4") (pin "7") (pinfunction "O_7") (pintype "output"))
      (node (ref "U9") (pin "14") (pinfunction "OUT_14") (pintype "output"))
      (node (ref "X3") (pin "4") (pinfunction "4_4") (pintype "passive"))
    )
    (net (code "104") (name "Net-(U4B-O)") (class "Default")
      (node (ref "PORTC") (pin "3") (pinfunction "3_3") (pintype "passive"))
      (node (ref "U4") (pin "5") (pinfunction "O_5") (pintype "output"))
      (node (ref "U9") (pin "1") (pinfunction "OUT_1") (pintype "output"))
      (node (ref "X3") (pin "3") (pinfunction "3_3") (pintype "passive"))
    )
    (net (code "105") (name "Net-(U7-RS)") (class "Default")
      (node (ref "R61") (pin "1") (pinfunction "1_1") (pintype "passive"))
      (node (ref "U7") (pin "8") (pinfunction "RS_8") (pintype "input"))
      (node (ref "U7B") (pin "8") (pinfunction "RS_8") (pintype "bidirectional"))
    )
    (net (code "106") (name "Net-(U8-VOUT)") (class "Default")
      (node (ref "D1") (pin "C") (pinfunction "C_C") (pintype "passive"))
      (node (ref "D3") (pin "C") (pinfunction "C_C") (pintype "passive"))
      (node (ref "L1") (pin "2") (pinfunction "2_2") (pintype "passive"))
      (node (ref "U8") (pin "2") (pinfunction "VOUT_2") (pintype "bidirectional"))
      (node (ref "U8B") (pin "7") (pinfunction "OUT_7") (pintype "passive"))
    )
    (net (code "107") (name "Net-(U10A--IN)") (class "Default")
      (node (ref "R1") (pin "1") (pinfunction "1_1") (pintype "passive"))
      (node (ref "R2") (pin "2") (pinfunction "2_2") (pintype "passive"))
      (node (ref "U10") (pin "13") (pinfunction "-IN_13") (pintype "input"))
      (node (ref "U10") (pin "2") (pinfunction "-IN_2") (pintype "input"))
      (node (ref "U10") (pin "6") (pinfunction "-IN_6") (pintype "input"))
      (node (ref "U10") (pin "9") (pinfunction "-IN_9") (pintype "input"))
      (node (ref "U9") (pin "13") (pinfunction "-IN_13") (pintype "input"))
      (node (ref "U9") (pin "2") (pinfunction "-IN_2") (pintype "input"))
      (node (ref "U9") (pin "6") (pinfunction "-IN_6") (pintype "input"))
      (node (ref "U9") (pin "9") (pinfunction "-IN_9") (pintype "input"))
    )
    (net (code "108") (name "Net-(U10A-OUT)") (class "Default")
      (node (ref "PORTC") (pin "9") (pinfunction "9_9") (pintype "passive"))
      (node (ref "U10") (pin "1") (pinfunction "OUT_1") (pintype "output"))
      (node (ref "U6") (pin "5") (pinfunction "O_5") (pintype "output"))
      (node (ref "X3") (pin "7") (pinfunction "7_7") (pintype "passive"))
    )
    (net (code "109") (name "Net-(U10B-OUT)") (class "Default")
      (node (ref "PORTC") (pin "7") (pinfunction "7_7") (pintype "passive"))
      (node (ref "U10") (pin "7") (pinfunction "OUT_7") (pintype "output"))
      (node (ref "U5") (pin "7") (pinfunction "O_7") (pintype "output"))
      (node (ref "X3") (pin "5") (pinfunction "5_5") (pintype "passive"))
    )
    (net (code "110") (name "Net-(U10C-OUT)") (class "Default")
      (node (ref "PORTC") (pin "8") (pinfunction "8_8") (pintype "passive"))
      (node (ref "U10") (pin "8") (pinfunction "OUT_8") (pintype "output"))
      (node (ref "U5") (pin "5") (pinfunction "O_5") (pintype "output"))
      (node (ref "X3") (pin "6") (pinfunction "6_6") (pintype "passive"))
    )
    (net (code "111") (name "Net-(U10D-OUT)") (class "Default")
      (node (ref "PORTC") (pin "10") (pinfunction "10_10") (pintype "passive"))
      (node (ref "U10") (pin "14") (pinfunction "OUT_14") (pintype "output"))
      (node (ref "U6") (pin "7") (pinfunction "O_7") (pintype "output"))
      (node (ref "X3") (pin "8") (pinfunction "8_8") (pintype "passive"))
    )
    (net (code "112") (name "Net-(U11A-QA)") (class "Default")
      (node (ref "R3") (pin "1") (pinfunction "1_1") (pintype "passive"))
      (node (ref "U11") (pin "15") (pinfunction "QA_15") (pintype "tri_state"))
      (node (ref "U12") (pin "1") (pinfunction "I1_1") (pintype "input"))
    )
    (net (code "113") (name "Net-(U11A-QB)") (class "Default")
      (node (ref "R4") (pin "1") (pinfunction "1_1") (pintype "passive"))
      (node (ref "U11") (pin "1") (pinfunction "QB_1") (pintype "tri_state"))
      (node (ref "U12") (pin "2") (pinfunction "I2_2") (pintype "input"))
    )
    (net (code "114") (name "Net-(U11A-QC)") (class "Default")
      (node (ref "R5") (pin "1") (pinfunction "1_1") (pintype "passive"))
      (node (ref "U11") (pin "2") (pinfunction "QC_2") (pintype "tri_state"))
      (node (ref "U12") (pin "3") (pinfunction "I3_3") (pintype "input"))
    )
    (net (code "115") (name "Net-(U11A-QD)") (class "Default")
      (node (ref "R6") (pin "1") (pinfunction "1_1") (pintype "passive"))
      (node (ref "U11") (pin "3") (pinfunction "QD_3") (pintype "tri_state"))
      (node (ref "U12") (pin "4") (pinfunction "I4_4") (pintype "input"))
    )
    (net (code "116") (name "Net-(U11A-QE)") (class "Default")
      (node (ref "R7") (pin "1") (pinfunction "1_1") (pintype "passive"))
      (node (ref "U11") (pin "4") (pinfunction "QE_4") (pintype "tri_state"))
      (node (ref "U12") (pin "5") (pinfunction "I5_5") (pintype "input"))
    )
    (net (code "117") (name "Net-(U11A-QF)") (class "Default")
      (node (ref "R8") (pin "1") (pinfunction "1_1") (pintype "passive"))
      (node (ref "U11") (pin "5") (pinfunction "QF_5") (pintype "tri_state"))
      (node (ref "U12") (pin "6") (pinfunction "I6_6") (pintype "input"))
    )
    (net (code "118") (name "Net-(U11A-QG)") (class "Default")
      (node (ref "R9") (pin "1") (pinfunction "1_1") (pintype "passive"))
      (node (ref "U11") (pin "6") (pinfunction "QG_6") (pintype "tri_state"))
      (node (ref "U12") (pin "7") (pinfunction "I7_7") (pintype "input"))
    )
    (net (code "119") (name "Net-(U11A-QH)") (class "Default")
      (node (ref "R10") (pin "1") (pinfunction "1_1") (pintype "passive"))
      (node (ref "U11") (pin "7") (pinfunction "QH_7") (pintype "tri_state"))
      (node (ref "U12") (pin "8") (pinfunction "I8_8") (pintype "input"))
    )
    (net (code "120") (name "Net-(U13A-QA)") (class "Default")
      (node (ref "R11") (pin "1") (pinfunction "1_1") (pintype "passive"))
      (node (ref "U13") (pin "15") (pinfunction "QA_15") (pintype "tri_state"))
      (node (ref "U14") (pin "1") (pinfunction "I1_1") (pintype "input"))
    )
    (net (code "121") (name "Net-(U13A-QB)") (class "Default")
      (node (ref "R12") (pin "1") (pinfunction "1_1") (pintype "passive"))
      (node (ref "U13") (pin "1") (pinfunction "QB_1") (pintype "tri_state"))
      (node (ref "U14") (pin "2") (pinfunction "I2_2") (pintype "input"))
    )
    (net (code "122") (name "Net-(U13A-QC)") (class "Default")
      (node (ref "R13") (pin "1") (pinfunction "1_1") (pintype "passive"))
      (node (ref "U13") (pin "2") (pinfunction "QC_2") (pintype "tri_state"))
      (node (ref "U14") (pin "3") (pinfunction "I3_3") (pintype "input"))
    )
    (net (code "123") (name "Net-(U13A-QD)") (class "Default")
      (node (ref "R14") (pin "1") (pinfunction "1_1") (pintype "passive"))
      (node (ref "U13") (pin "3") (pinfunction "QD_3") (pintype "tri_state"))
      (node (ref "U14") (pin "4") (pinfunction "I4_4") (pintype "input"))
    )
    (net (code "124") (name "Net-(U13A-QE)") (class "Default")
      (node (ref "R15") (pin "1") (pinfunction "1_1") (pintype "passive"))
      (node (ref "U13") (pin "4") (pinfunction "QE_4") (pintype "tri_state"))
      (node (ref "U14") (pin "5") (pinfunction "I5_5") (pintype "input"))
    )
    (net (code "125") (name "Net-(U13A-QF)") (class "Default")
      (node (ref "R16") (pin "1") (pinfunction "1_1") (pintype "passive"))
      (node (ref "U13") (pin "5") (pinfunction "QF_5") (pintype "tri_state"))
      (node (ref "U14") (pin "6") (pinfunction "I6_6") (pintype "input"))
    )
    (net (code "126") (name "Net-(U13A-QG)") (class "Default")
      (node (ref "R17") (pin "1") (pinfunction "1_1") (pintype "passive"))
      (node (ref "U13") (pin "6") (pinfunction "QG_6") (pintype "tri_state"))
      (node (ref "U14") (pin "7") (pinfunction "I7_7") (pintype "input"))
    )
    (net (code "127") (name "Net-(U13A-QH)") (class "Default")
      (node (ref "R18") (pin "1") (pinfunction "1_1") (pintype "passive"))
      (node (ref "U13") (pin "7") (pinfunction "QH_7") (pintype "tri_state"))
      (node (ref "U14") (pin "8") (pinfunction "I8_8") (pintype "input"))
    )
    (net (code "128") (name "OLAT") (class "Default")
      (node (ref "R21") (pin "1") (pinfunction "1_1") (pintype "passive"))
      (node (ref "U$1") (pin "PA8") (pinfunction "PA8_PA8") (pintype "bidirectional"))
      (node (ref "U11") (pin "12") (pinfunction "RCK_12") (pintype "input"))
      (node (ref "U13") (pin "12") (pinfunction "RCK_12") (pintype "input"))
    )
    (net (code "129") (name "SCK") (class "Default")
      (node (ref "JP2") (pin "3") (pinfunction "3_3") (pintype "passive"))
      (node (ref "R19") (pin "1") (pinfunction "1_1") (pintype "passive"))
      (node (ref "U$1") (pin "PB3") (pinfunction "PB3_PB3") (pintype "bidirectional"))
      (node (ref "U11") (pin "11") (pinfunction "SCK_11") (pintype "input"))
      (node (ref "U13") (pin "11") (pinfunction "SCK_11") (pintype "input"))
    )
    (net (code "130") (name "SCK2") (class "Default")
      (node (ref "U$1") (pin "PB10") (pinfunction "PB10_PB10") (pintype "bidirectional"))
      (node (ref "U1") (pin "7") (pinfunction "CLK_7") (pintype "input"))
      (node (ref "U2") (pin "7") (pinfunction "CLK_7") (pintype "input"))
    )
    (net (code "131") (name "SLNK1") (class "Default")
      (node (ref "SJ17") (pin "P$1") (pinfunction "1_P$1") (pintype "passive"))
      (node (ref "U11") (pin "9") (pinfunction "QH*_9") (pintype "tri_state"))
      (node (ref "U13") (pin "14") (pinfunction "SER_14") (pintype "input"))
    )
    (net (code "132") (name "SLNK2") (class "Default")
      (node (ref "SJ16") (pin "P$1") (pinfunction "1_P$1") (pintype "passive"))
      (node (ref "U13") (pin "9") (pinfunction "QH*_9") (pintype "tri_state"))
    )
    (net (code "133") (name "SLNK3") (class "Default")
      (node (ref "SJ19") (pin "P$1") (pinfunction "1_P$1") (pintype "passive"))
      (node (ref "U1") (pin "13") (pinfunction "QH_13") (pintype "output"))
      (node (ref "U2") (pin "1") (pinfunction "SER_1") (pintype "input"))
    )
    (net (code "134") (name "SRV1") (class "Default")
      (node (ref "JP5") (pin "2") (pinfunction "2_2") (pintype "passive"))
      (node (ref "R24") (pin "2") (pinfunction "2_2") (pintype "passive"))
      (node (ref "U$1") (pin "PC9") (pinfunction "PC9_PC9") (pintype "bidirectional"))
    )
    (net (code "135") (name "SRV2") (class "Default")
      (node (ref "JP5") (pin "1") (pinfunction "1_1") (pintype "passive"))
      (node (ref "R25") (pin "2") (pinfunction "2_2") (pintype "passive"))
      (node (ref "U$1") (pin "PC7") (pinfunction "PC7_PC7") (pintype "bidirectional"))
    )
    (net (code "136") (name "SRV3") (class "Default")
      (node (ref "JP6") (pin "2") (pinfunction "2_2") (pintype "passive"))
      (node (ref "R26") (pin "2") (pinfunction "2_2") (pintype "passive"))
      (node (ref "U$1") (pin "PC8") (pinfunction "PC8_PC8") (pintype "bidirectional"))
    )
    (net (code "137") (name "SRV4") (class "Default")
      (node (ref "JP6") (pin "1") (pinfunction "1_1") (pintype "passive"))
      (node (ref "R27") (pin "2") (pinfunction "2_2") (pintype "passive"))
      (node (ref "U$1") (pin "PC6") (pinfunction "PC6_PC6") (pintype "bidirectional"))
    )
    (net (code "138") (name "SRV5") (class "Default")
      (node (ref "JP7") (pin "2") (pinfunction "2_2") (pintype "passive"))
      (node (ref "R64") (pin "2") (pinfunction "2_2") (pintype "passive"))
      (node (ref "U$1") (pin "PF1-PH1") (pinfunction "PF1-PH1_PF1-PH1") (pintype "bidirectional"))
    )
    (net (code "139") (name "SRV6") (class "Default")
      (node (ref "JP7") (pin "1") (pinfunction "1_1") (pintype "passive"))
      (node (ref "R65") (pin "2") (pinfunction "2_2") (pintype "passive"))
      (node (ref "U$1") (pin "PA15") (pinfunction "PA15_PA15") (pintype "bidirectional"))
    )
    (net (code "140") (name "SRV7") (class "Default")
      (node (ref "JP8") (pin "2") (pinfunction "2_2") (pintype "passive"))
      (node (ref "R66") (pin "2") (pinfunction "2_2") (pintype "passive"))
      (node (ref "U$1") (pin "PC12") (pinfunction "PC12_PC12") (pintype "bidirectional"))
    )
    (net (code "141") (name "SRV8") (class "Default")
      (node (ref "JP8") (pin "1") (pinfunction "1_1") (pintype "passive"))
      (node (ref "R67") (pin "2") (pinfunction "2_2") (pintype "passive"))
      (node (ref "U$1") (pin "PD2") (pinfunction "PD2_PD2") (pintype "bidirectional"))
    )
    (net (code "142") (name "TDRV1") (class "Default")
      (node (ref "U$1") (pin "PB12") (pinfunction "PB12_PB12") (pintype "bidirectional"))
      (node (ref "U10") (pin "12") (pinfunction "+IN_12") (pintype "input"))
      (node (ref "U6") (pin "2") (pinfunction "I_2") (pintype "input"))
    )
    (net (code "143") (name "TDRV2") (class "Default")
      (node (ref "U$1") (pin "PB2") (pinfunction "PB2_PB2") (pintype "bidirectional"))
      (node (ref "U10") (pin "3") (pinfunction "+IN_3") (pintype "input"))
      (node (ref "U6") (pin "4") (pinfunction "I_4") (pintype "input"))
    )
    (net (code "144") (name "TDRV3") (class "Default")
      (node (ref "U$1") (pin "PB15") (pinfunction "PB15_PB15") (pintype "bidirectional"))
      (node (ref "U10") (pin "10") (pinfunction "+IN_10") (pintype "input"))
      (node (ref "U5") (pin "4") (pinfunction "I_4") (pintype "input"))
    )
    (net (code "145") (name "TDRV4") (class "Default")
      (node (ref "U$1") (pin "PB1") (pinfunction "PB1_PB1") (pintype "bidirectional"))
      (node (ref "U10") (pin "5") (pinfunction "+IN_5") (pintype "input"))
      (node (ref "U5") (pin "2") (pinfunction "I_2") (pintype "input"))
    )
    (net (code "146") (name "TDRV5") (class "Default")
      (node (ref "U$1") (pin "PA0") (pinfunction "PA0_PA0") (pintype "bidirectional"))
      (node (ref "U4") (pin "2") (pinfunction "I_2") (pintype "input"))
      (node (ref "U9") (pin "12") (pinfunction "+IN_12") (pintype "input"))
    )
    (net (code "147") (name "TDRV6") (class "Default")
      (node (ref "U$1") (pin "PA4") (pinfunction "PA4_PA4") (pintype "bidirectional"))
      (node (ref "U4") (pin "4") (pinfunction "I_4") (pintype "input"))
      (node (ref "U9") (pin "3") (pinfunction "+IN_3") (pintype "input"))
    )
    (net (code "148") (name "TDRV7") (class "Default")
      (node (ref "U$1") (pin "PC3") (pinfunction "PC3_PC3") (pintype "bidirectional"))
      (node (ref "U3") (pin "4") (pinfunction "I_4") (pintype "input"))
      (node (ref "U9") (pin "10") (pinfunction "+IN_10") (pintype "input"))
    )
    (net (code "149") (name "TDRV8") (class "Default")
      (node (ref "U$1") (pin "PC0") (pinfunction "PC0_PC0") (pintype "bidirectional"))
      (node (ref "U3") (pin "2") (pinfunction "I_2") (pintype "input"))
      (node (ref "U9") (pin "5") (pinfunction "+IN_5") (pintype "input"))
    )
    (net (code "150") (name "V+") (class "Default")
      (node (ref "C1") (pin "1") (pinfunction "1_1") (pintype "passive"))
      (node (ref "C2") (pin "+") (pinfunction "+_+") (pintype "passive"))
      (node (ref "L1") (pin "1") (pinfunction "1_1") (pintype "passive"))
      (node (ref "U$1") (pin "E5V") (pinfunction "E5V_E5V") (pintype "power_in"))
      (node (ref "U8") (pin "3") (pinfunction "FB_3") (pintype "bidirectional"))
      (node (ref "U8B") (pin "1") (pinfunction "FB_1") (pintype "input"))
    )
    (net (code "151") (name "unconnected-(H1-MOUNT-PadB3,3)") (class "Default")
      (node (ref "H1") (pin "B3,3") (pinfunction "MOUNT_B3,3") (pintype "passive"))
    )
    (net (code "152") (name "unconnected-(H2-MOUNT-PadB3,3)") (class "Default")
      (node (ref "H2") (pin "B3,3") (pinfunction "MOUNT_B3,3") (pintype "passive"))
    )
    (net (code "153") (name "unconnected-(H3-MOUNT-PadB3,3)") (class "Default")
      (node (ref "H3") (pin "B3,3") (pinfunction "MOUNT_B3,3") (pintype "passive"))
    )
    (net (code "154") (name "unconnected-(H4-MOUNT-PadB3,3)") (class "Default")
      (node (ref "H4") (pin "B3,3") (pinfunction "MOUNT_B3,3") (pintype "passive"))
    )
    (net (code "155") (name "unconnected-(U$1-PadBOOT0)") (class "Default")
      (node (ref "U$1") (pin "BOOT0") (pinfunction "BOOT0_BOOT0") (pintype "bidirectional"))
    )
    (net (code "156") (name "unconnected-(U$1-PadIOREF2)") (class "Default")
      (node (ref "U$1") (pin "IOREF2") (pinfunction "IOREF2_IOREF2") (pintype "input"))
    )
    (net (code "157") (name "unconnected-(U$1-PadNC1-PF7)") (class "Default")
      (node (ref "U$1") (pin "NC1-PF7") (pinfunction "NC1-PF7_NC1-PF7") (pintype "bidirectional"))
    )
    (net (code "158") (name "unconnected-(U$1-PadNC2-PF6)") (class "Default")
      (node (ref "U$1") (pin "NC2-PF6") (pinfunction "NC2-PF6_NC2-PF6") (pintype "bidirectional"))
    )
    (net (code "159") (name "unconnected-(U$1-PadNC3)") (class "Default")
      (node (ref "U$1") (pin "NC3") (pinfunction "NC3_NC3") (pintype "no_connect"))
    )
    (net (code "160") (name "unconnected-(U$1-PadNC4)") (class "Default")
      (node (ref "U$1") (pin "NC4") (pinfunction "NC4_NC4") (pintype "no_connect"))
    )
    (net (code "161") (name "unconnected-(U$1-PadNC5-PD8)") (class "Default")
      (node (ref "U$1") (pin "NC5-PD8") (pinfunction "NC5-PD8_NC5-PD8") (pintype "bidirectional"))
    )
    (net (code "162") (name "unconnected-(U$1-PadNC6-PB11)") (class "Default")
      (node (ref "U$1") (pin "NC6-PB11") (pinfunction "NC6-PB11_NC6-PB11") (pintype "no_connect"))
    )
    (net (code "163") (name "unconnected-(U$1-PadNC7-PF5)") (class "Default")
      (node (ref "U$1") (pin "NC7-PF5") (pinfunction "NC7-PF5_NC7-PF5") (pintype "bidirectional"))
    )
    (net (code "164") (name "unconnected-(U$1-PadNC8-PF4)") (class "Default")
      (node (ref "U$1") (pin "NC8-PF4") (pinfunction "NC8-PF4_NC8-PF4") (pintype "bidirectional"))
    )
    (net (code "165") (name "unconnected-(U$1-PadNRESET)") (class "Default")
      (node (ref "U$1") (pin "NRESET") (pinfunction "NRESET_NRESET") (pintype "input"))
    )
    (net (code "166") (name "unconnected-(U$1-PadPA1)") (class "Default")
      (node (ref "U$1") (pin "PA1") (pinfunction "PA1_PA1") (pintype "bidirectional"))
    )
    (net (code "167") (name "unconnected-(U$1-PadPA2)") (class "Default")
      (node (ref "U$1") (pin "PA2") (pinfunction "PA2_PA2") (pintype "bidirectional"))
    )
    (net (code "168") (name "unconnected-(U$1-PadPA3)") (class "Default")
      (node (ref "U$1") (pin "PA3") (pinfunction "PA3_PA3") (pintype "bidirectional"))
    )
    (net (code "169") (name "unconnected-(U$1-PadPA5)") (class "Default")
      (node (ref "U$1") (pin "PA5") (pinfunction "PA5_PA5") (pintype "bidirectional"))
    )
    (net (code "170") (name "unconnected-(U$1-PadPA7)") (class "Default")
      (node (ref "U$1") (pin "PA7") (pinfunction "PA7_PA7") (pintype "bidirectional"))
    )
    (net (code "171") (name "unconnected-(U$1-PadPA9)") (class "Default")
      (node (ref "U$1") (pin "PA9") (pinfunction "PA9_PA9") (pintype "bidirectional"))
    )
    (net (code "172") (name "unconnected-(U$1-PadPA10)") (class "Default")
      (node (ref "U$1") (pin "PA10") (pinfunction "PA10_PA10") (pintype "bidirectional"))
    )
    (net (code "173") (name "unconnected-(U$1-PadPA11)") (class "Default")
      (node (ref "U$1") (pin "PA11") (pinfunction "PA11_PA11") (pintype "bidirectional"))
    )
    (net (code "174") (name "unconnected-(U$1-PadPA12)") (class "Default")
      (node (ref "U$1") (pin "PA12") (pinfunction "PA12_PA12") (pintype "bidirectional"))
    )
    (net (code "175") (name "unconnected-(U$1-PadPA13)") (class "Default")
      (node (ref "U$1") (pin "PA13") (pinfunction "PA13_PA13") (pintype "bidirectional"))
    )
    (net (code "176") (name "unconnected-(U$1-PadPA14)") (class "Default")
      (node (ref "U$1") (pin "PA14") (pinfunction "PA14_PA14") (pintype "bidirectional"))
    )
    (net (code "177") (name "unconnected-(U$1-PadPB0)") (class "Default")
      (node (ref "U$1") (pin "PB0") (pinfunction "PB0_PB0") (pintype "bidirectional"))
    )
    (net (code "178") (name "unconnected-(U$1-PadPB13)") (class "Default")
      (node (ref "U$1") (pin "PB13") (pinfunction "PB13_PB13") (pintype "bidirectional"))
    )
    (net (code "179") (name "unconnected-(U$1-PadPC1)") (class "Default")
      (node (ref "U$1") (pin "PC1") (pinfunction "PC1_PC1") (pintype "bidirectional"))
    )
    (net (code "180") (name "unconnected-(U$1-PadPC4)") (class "Default")
      (node (ref "U$1") (pin "PC4") (pinfunction "PC4_PC4") (pintype "bidirectional"))
    )
    (net (code "181") (name "unconnected-(U$1-PadPC5)") (class "Default")
      (node (ref "U$1") (pin "PC5") (pinfunction "PC5_PC5") (pintype "bidirectional"))
    )
    (net (code "182") (name "unconnected-(U$1-PadPC13)") (class "Default")
      (node (ref "U$1") (pin "PC13") (pinfunction "PC13_PC13") (pintype "bidirectional"))
    )
    (net (code "183") (name "unconnected-(U$1-PadPC14)") (class "Default")
      (node (ref "U$1") (pin "PC14") (pinfunction "PC14_PC14") (pintype "bidirectional"))
    )
    (net (code "184") (name "unconnected-(U$1-PadPC15)") (class "Default")
      (node (ref "U$1") (pin "PC15") (pinfunction "PC15_PC15") (pintype "bidirectional"))
    )
    (net (code "185") (name "unconnected-(U$1-PadPF0-PH0)") (class "Default")
      (node (ref "U$1") (pin "PF0-PH0") (pinfunction "PF0-PH0_PF0-PH0") (pintype "bidirectional"))
    )
  )
)
